# Reach_A0.net
KiCad netlist of a schematic drawn in EAGLE
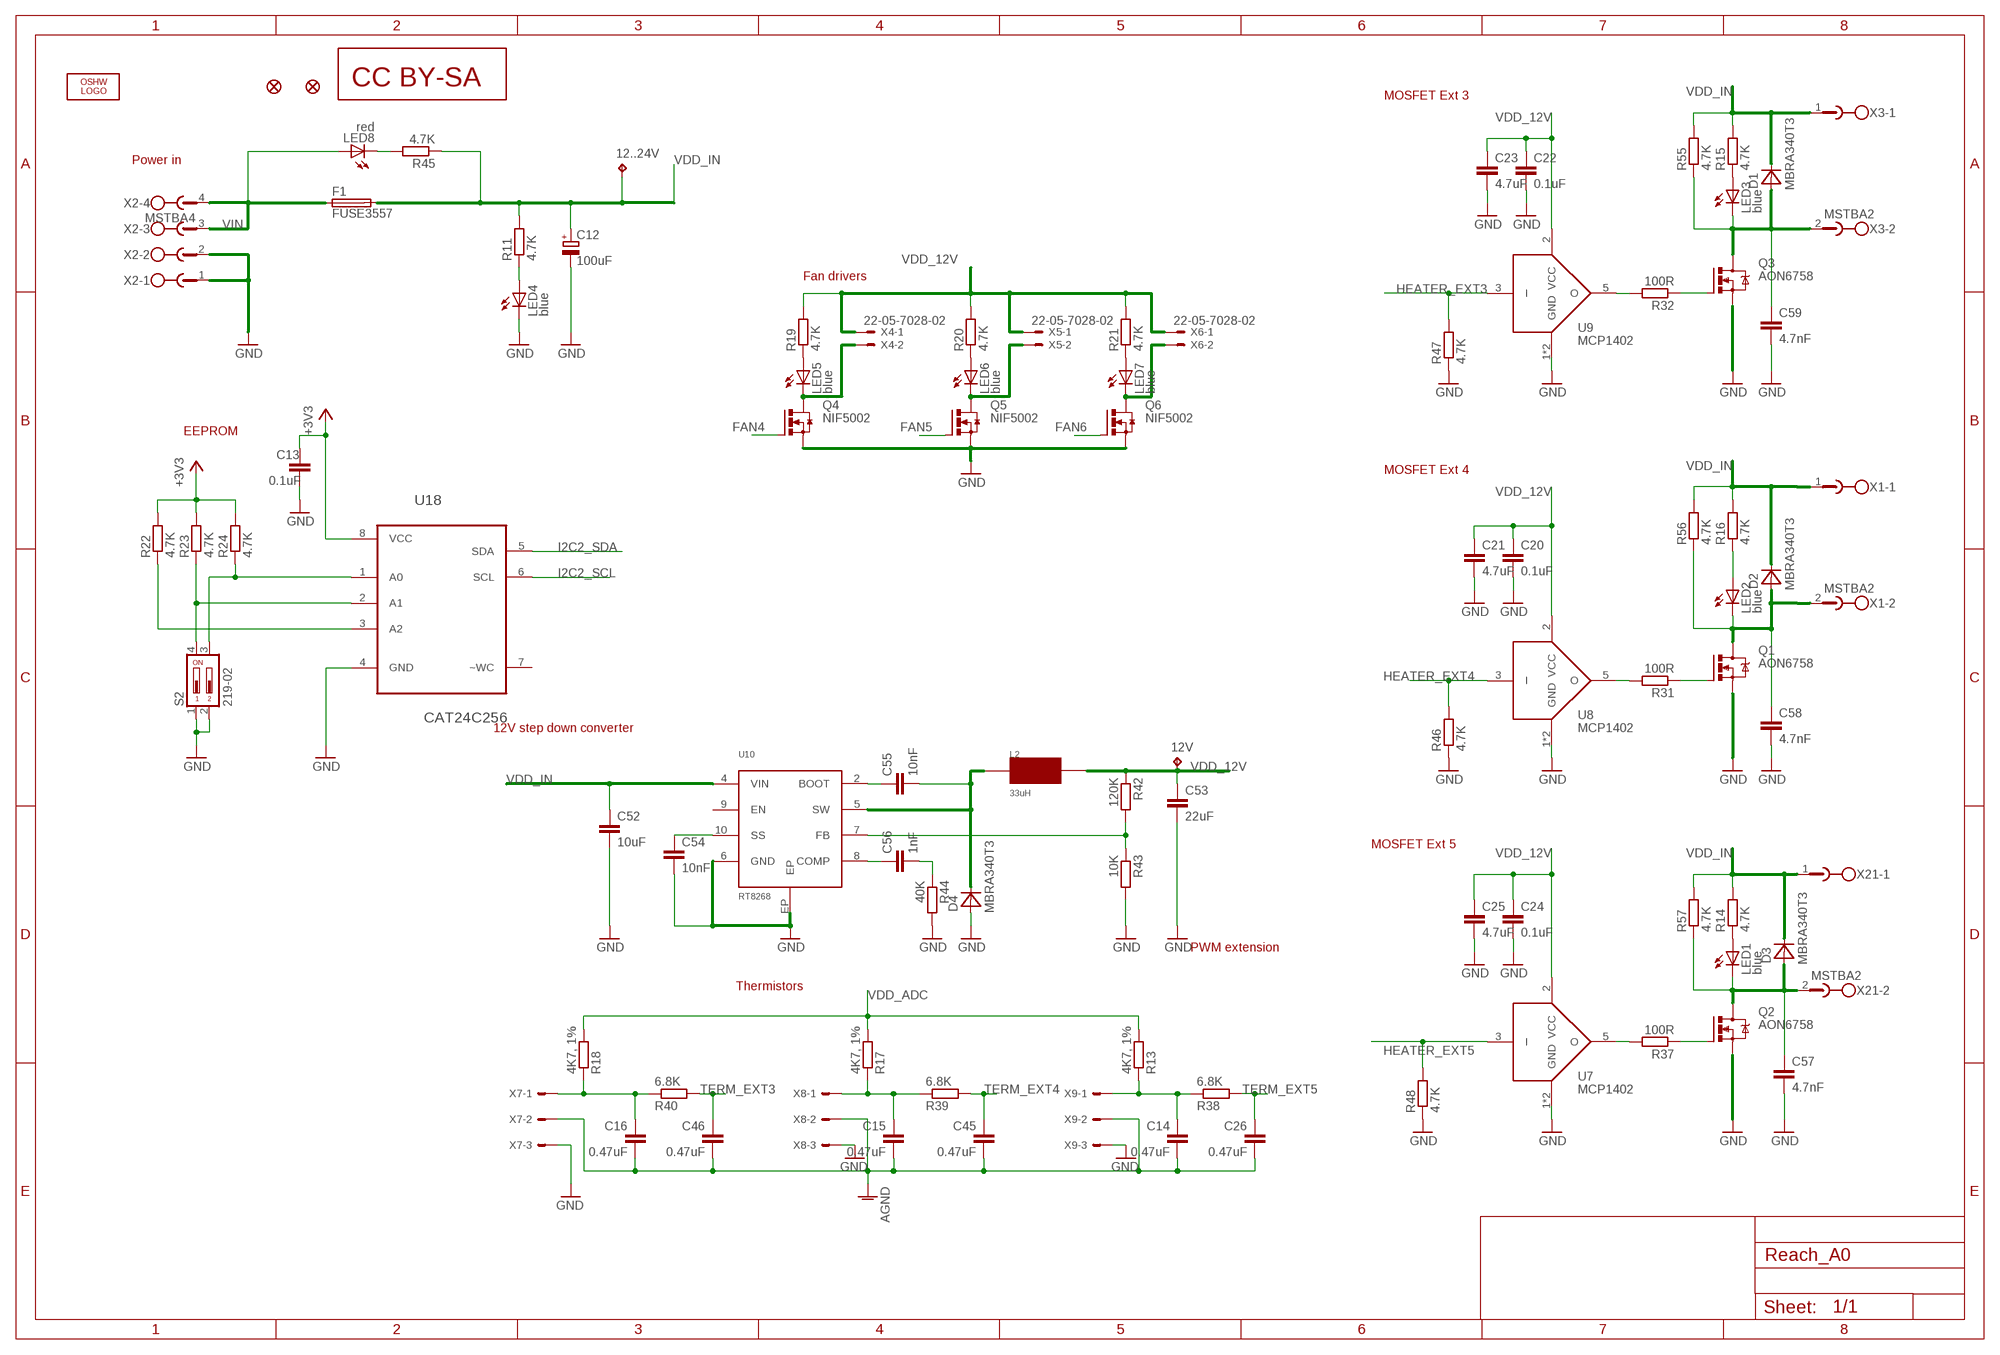
[diagram p0: schematic, sheet 1, part 1 of 2]
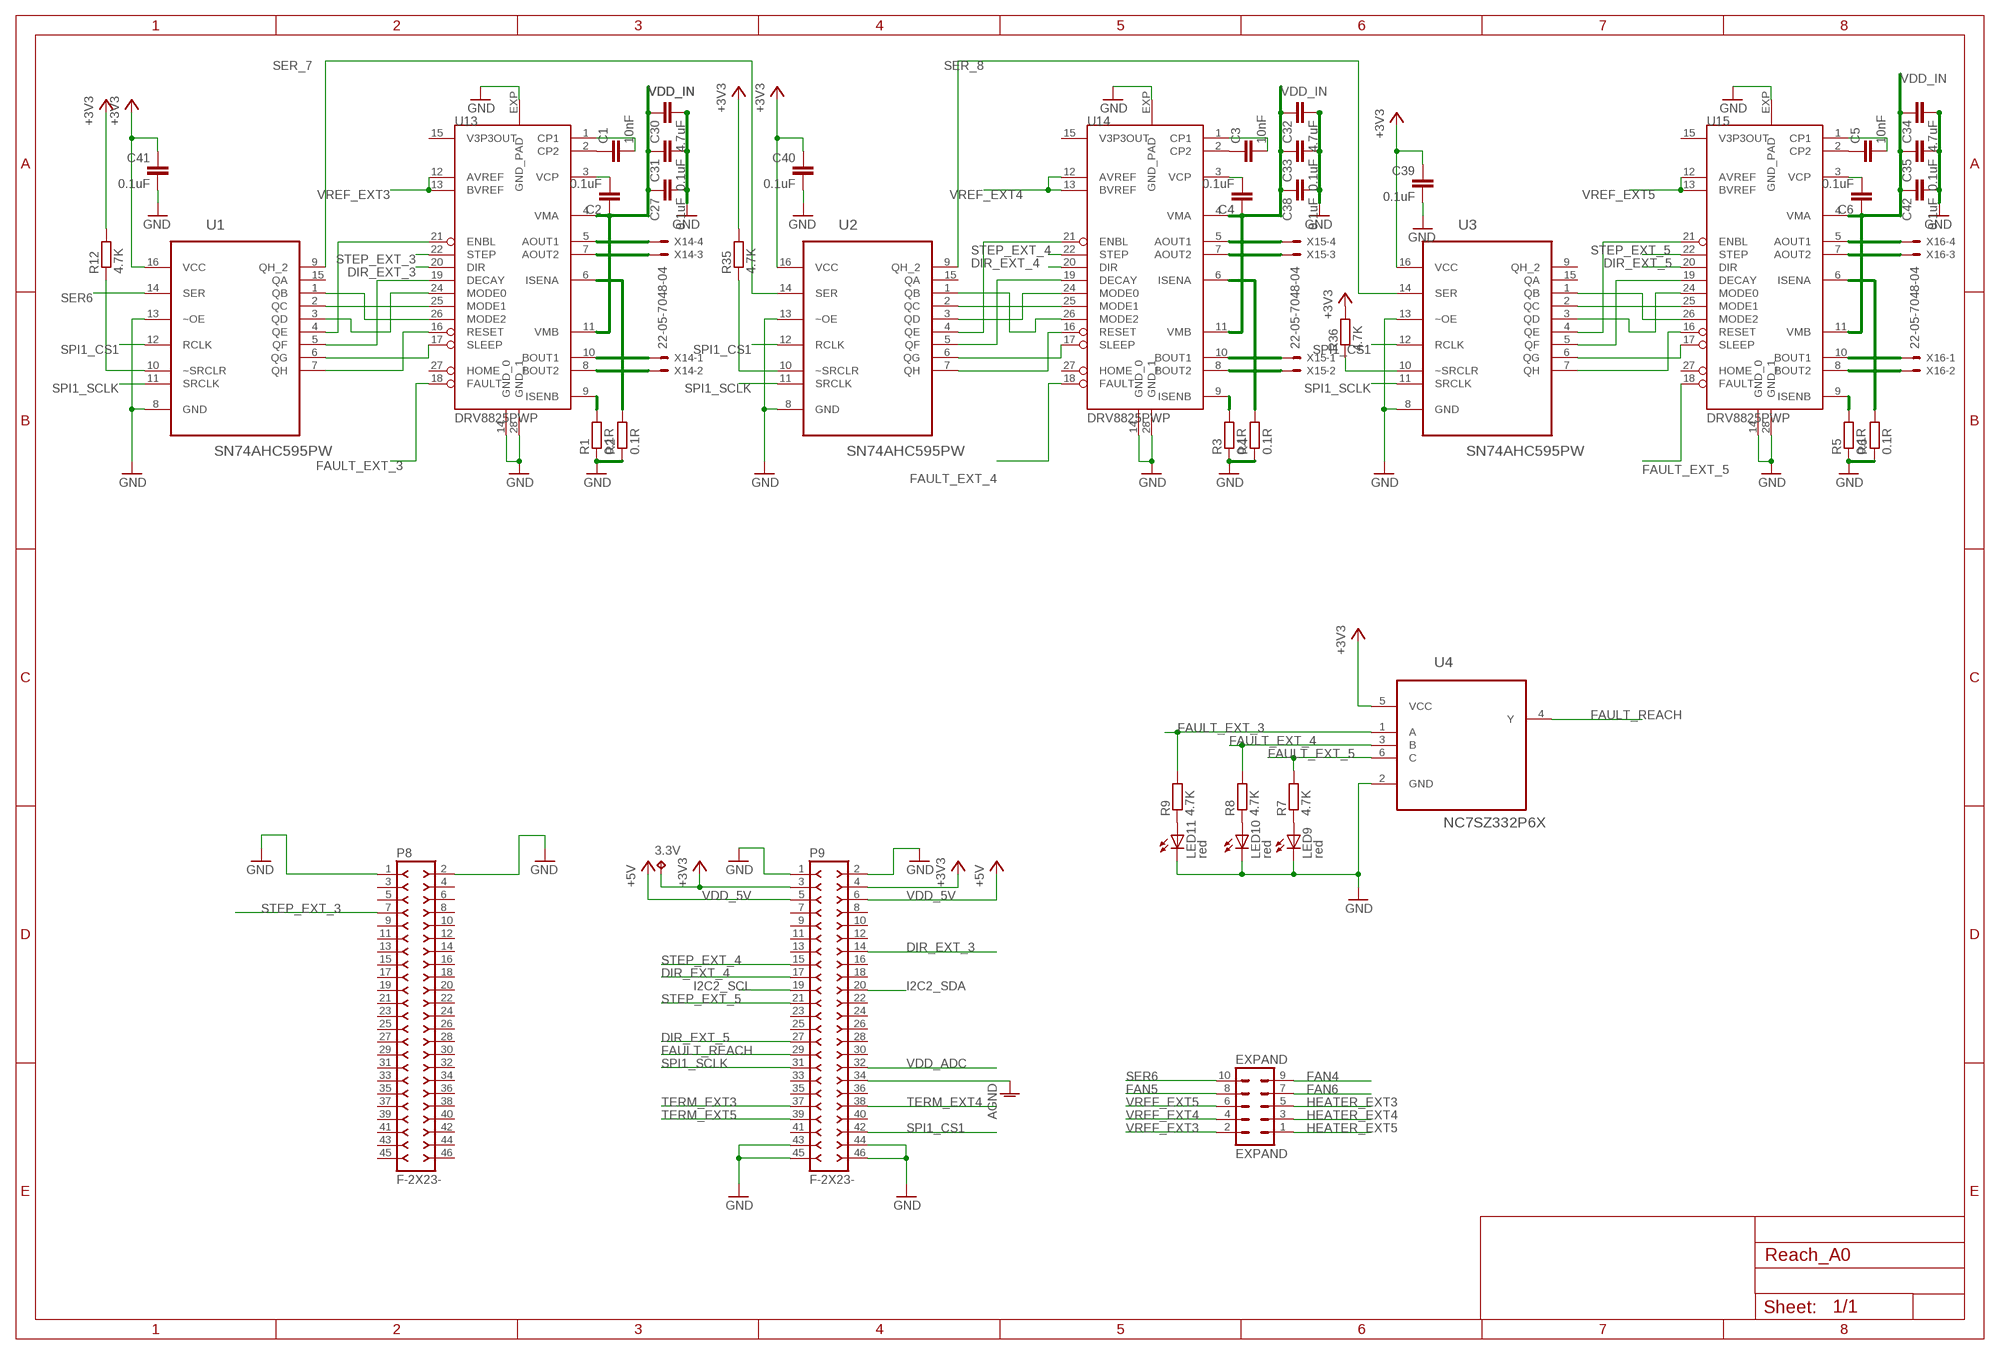
[diagram p1: schematic, sheet 1, part 2 of 2]

(export (version "E")
  (design (tool "Eeschema 10.0.6"))
  (components
    (comp (ref "3.3V")
      (value "TPB1,27")
      (footprint "eagle-import:B1,27")
      (libsource (lib "eagle-import") (part "TPB1,27"))
    )
    (comp (ref "12..24V")
      (value "TPB1,27")
      (footprint "eagle-import:B1,27")
      (libsource (lib "eagle-import") (part "TPB1,27"))
    )
    (comp (ref "12V")
      (value "TPB1,27")
      (footprint "eagle-import:B1,27")
      (libsource (lib "eagle-import") (part "TPB1,27"))
    )
    (comp (ref "C1")
      (value "10nF")
      (footprint "eagle-import:C0402")
      (libsource (lib "eagle-import") (part "C-EUC0402"))
    )
    (comp (ref "C2")
      (value "0.1uF")
      (footprint "eagle-import:C0402")
      (libsource (lib "eagle-import") (part "C-EUC0402"))
    )
    (comp (ref "C3")
      (value "10nF")
      (footprint "eagle-import:C0402")
      (libsource (lib "eagle-import") (part "C-EUC0402"))
    )
    (comp (ref "C4")
      (value "0.1uF")
      (footprint "eagle-import:C0402")
      (libsource (lib "eagle-import") (part "C-EUC0402"))
    )
    (comp (ref "C5")
      (value "10nF")
      (footprint "eagle-import:C0402")
      (libsource (lib "eagle-import") (part "C-EUC0402"))
    )
    (comp (ref "C6")
      (value "0.1uF")
      (footprint "eagle-import:C0402")
      (libsource (lib "eagle-import") (part "C-EUC0402"))
    )
    (comp (ref "C12")
      (value "100uF")
      (footprint "eagle-import:140CLH-0810")
      (libsource (lib "eagle-import") (part "CPOL-EU140CLH-0810"))
    )
    (comp (ref "C13")
      (value "0.1uF")
      (footprint "eagle-import:C0402")
      (libsource (lib "eagle-import") (part "C-EUC0402"))
    )
    (comp (ref "C14")
      (value "0.47uF")
      (footprint "eagle-import:C0402")
      (libsource (lib "eagle-import") (part "C-EUC0402"))
    )
    (comp (ref "C15")
      (value "0.47uF")
      (footprint "eagle-import:C0402")
      (libsource (lib "eagle-import") (part "C-EUC0402"))
    )
    (comp (ref "C16")
      (value "0.47uF")
      (footprint "eagle-import:C0402")
      (libsource (lib "eagle-import") (part "C-EUC0402"))
    )
    (comp (ref "C20")
      (value "0.1uF")
      (footprint "eagle-import:C0402")
      (libsource (lib "eagle-import") (part "C-EUC0402"))
    )
    (comp (ref "C21")
      (value "4.7uF")
      (footprint "eagle-import:C0402")
      (libsource (lib "eagle-import") (part "C-EUC0402"))
    )
    (comp (ref "C22")
      (value "0.1uF")
      (footprint "eagle-import:C0402")
      (libsource (lib "eagle-import") (part "C-EUC0402"))
    )
    (comp (ref "C23")
      (value "4.7uF")
      (footprint "eagle-import:C0402")
      (libsource (lib "eagle-import") (part "C-EUC0402"))
    )
    (comp (ref "C24")
      (value "0.1uF")
      (footprint "eagle-import:C0402")
      (libsource (lib "eagle-import") (part "C-EUC0402"))
    )
    (comp (ref "C25")
      (value "4.7uF")
      (footprint "eagle-import:C0402")
      (libsource (lib "eagle-import") (part "C-EUC0402"))
    )
    (comp (ref "C26")
      (value "0.47uF")
      (footprint "eagle-import:C0402")
      (libsource (lib "eagle-import") (part "C-EUC0402"))
    )
    (comp (ref "C27")
      (value "0.1uF")
      (footprint "eagle-import:C0402")
      (libsource (lib "eagle-import") (part "C-EUC0402"))
    )
    (comp (ref "C30")
      (value "4.7uF")
      (footprint "eagle-import:C0603")
      (libsource (lib "eagle-import") (part "C-EUC0603"))
    )
    (comp (ref "C31")
      (value "0.1uF")
      (footprint "eagle-import:C0402")
      (libsource (lib "eagle-import") (part "C-EUC0402"))
    )
    (comp (ref "C32")
      (value "4.7uF")
      (footprint "eagle-import:C0603")
      (libsource (lib "eagle-import") (part "C-EUC0603"))
    )
    (comp (ref "C33")
      (value "0.1uF")
      (footprint "eagle-import:C0402")
      (libsource (lib "eagle-import") (part "C-EUC0402"))
    )
    (comp (ref "C34")
      (value "4.7uF")
      (footprint "eagle-import:C0603")
      (libsource (lib "eagle-import") (part "C-EUC0603"))
    )
    (comp (ref "C35")
      (value "0.1uF")
      (footprint "eagle-import:C0402")
      (libsource (lib "eagle-import") (part "C-EUC0402"))
    )
    (comp (ref "C38")
      (value "0.1uF")
      (footprint "eagle-import:C0402")
      (libsource (lib "eagle-import") (part "C-EUC0402"))
    )
    (comp (ref "C39")
      (value "0.1uF")
      (footprint "eagle-import:C0402")
      (libsource (lib "eagle-import") (part "C-EUC0402"))
    )
    (comp (ref "C40")
      (value "0.1uF")
      (footprint "eagle-import:C0402")
      (libsource (lib "eagle-import") (part "C-EUC0402"))
    )
    (comp (ref "C41")
      (value "0.1uF")
      (footprint "eagle-import:C0402")
      (libsource (lib "eagle-import") (part "C-EUC0402"))
    )
    (comp (ref "C42")
      (value "0.1uF")
      (footprint "eagle-import:C0402")
      (libsource (lib "eagle-import") (part "C-EUC0402"))
    )
    (comp (ref "C45")
      (value "0.47uF")
      (footprint "eagle-import:C0402")
      (libsource (lib "eagle-import") (part "C-EUC0402"))
    )
    (comp (ref "C46")
      (value "0.47uF")
      (footprint "eagle-import:C0402")
      (libsource (lib "eagle-import") (part "C-EUC0402"))
    )
    (comp (ref "C52")
      (value "10uF")
      (footprint "eagle-import:C1206")
      (libsource (lib "eagle-import") (part "C-EUC1206"))
    )
    (comp (ref "C53")
      (value "22uF")
      (footprint "eagle-import:C0805")
      (libsource (lib "eagle-import") (part "C-EUC0805"))
    )
    (comp (ref "C54")
      (value "10nF")
      (footprint "eagle-import:C0402")
      (libsource (lib "eagle-import") (part "C-EUC0402"))
    )
    (comp (ref "C55")
      (value "10nF")
      (footprint "eagle-import:C0402")
      (libsource (lib "eagle-import") (part "C-EUC0402"))
    )
    (comp (ref "C56")
      (value "1nF")
      (footprint "eagle-import:C0402")
      (libsource (lib "eagle-import") (part "C-EUC0402"))
    )
    (comp (ref "C57")
      (value "4.7nF")
      (footprint "eagle-import:C0402")
      (libsource (lib "eagle-import") (part "C-EUC0402"))
    )
    (comp (ref "C58")
      (value "4.7nF")
      (footprint "eagle-import:C0402")
      (libsource (lib "eagle-import") (part "C-EUC0402"))
    )
    (comp (ref "C59")
      (value "4.7nF")
      (footprint "eagle-import:C0402")
      (libsource (lib "eagle-import") (part "C-EUC0402"))
    )
    (comp (ref "D1")
      (value "MBRA340T3")
      (footprint "eagle-import:SMA")
      (libsource (lib "eagle-import") (part "MBRA340T3"))
    )
    (comp (ref "D2")
      (value "MBRA340T3")
      (footprint "eagle-import:SMA")
      (libsource (lib "eagle-import") (part "MBRA340T3"))
    )
    (comp (ref "D3")
      (value "MBRA340T3")
      (footprint "eagle-import:SMA")
      (libsource (lib "eagle-import") (part "MBRA340T3"))
    )
    (comp (ref "D4")
      (value "MBRA340T3")
      (footprint "eagle-import:SMA")
      (libsource (lib "eagle-import") (part "MBRA340T3"))
    )
    (comp (ref "EXPAND")
      (value "EXPAND")
      (footprint "eagle-import:MA05-2")
      (libsource (lib "eagle-import") (part "MA05-2"))
    )
    (comp (ref "F1")
      (value "FUSE3557")
      (footprint "eagle-import:3557")
      (libsource (lib "eagle-import") (part "FUSE3557"))
    )
    (comp (ref "JP1")
      (value "FIDUCIAL1X2.5")
      (footprint "eagle-import:FIDUCIAL-1X2.5")
      (libsource (lib "eagle-import") (part "FIDUCIAL1X2.5"))
    )
    (comp (ref "JP2")
      (value "FIDUCIAL1X2.5")
      (footprint "eagle-import:FIDUCIAL-1X2.5")
      (libsource (lib "eagle-import") (part "FIDUCIAL1X2.5"))
    )
    (comp (ref "L2")
      (value "33uH")
      (footprint "eagle-import:NR8040T330")
      (libsource (lib "eagle-import") (part "RT8040T330"))
    )
    (comp (ref "LED1")
      (value "blue")
      (footprint "eagle-import:CHIP-LED0603")
      (libsource (lib "eagle-import") (part "LEDCHIP-LED0603"))
    )
    (comp (ref "LED2")
      (value "blue")
      (footprint "eagle-import:CHIP-LED0603")
      (libsource (lib "eagle-import") (part "LEDCHIP-LED0603"))
    )
    (comp (ref "LED3")
      (value "blue")
      (footprint "eagle-import:CHIP-LED0603")
      (libsource (lib "eagle-import") (part "LEDCHIP-LED0603"))
    )
    (comp (ref "LED4")
      (value "blue")
      (footprint "eagle-import:CHIP-LED0603")
      (libsource (lib "eagle-import") (part "LEDCHIP-LED0603"))
    )
    (comp (ref "LED5")
      (value "blue")
      (footprint "eagle-import:CHIP-LED0603")
      (libsource (lib "eagle-import") (part "LEDCHIP-LED0603"))
    )
    (comp (ref "LED6")
      (value "blue")
      (footprint "eagle-import:CHIP-LED0603")
      (libsource (lib "eagle-import") (part "LEDCHIP-LED0603"))
    )
    (comp (ref "LED7")
      (value "blue")
      (footprint "eagle-import:CHIP-LED0603")
      (libsource (lib "eagle-import") (part "LEDCHIP-LED0603"))
    )
    (comp (ref "LED8")
      (value "red")
      (footprint "eagle-import:CHIP-LED0603")
      (libsource (lib "eagle-import") (part "LEDCHIP-LED0603"))
    )
    (comp (ref "LED9")
      (value "red")
      (footprint "eagle-import:CHIP-LED0603")
      (libsource (lib "eagle-import") (part "LEDCHIP-LED0603"))
    )
    (comp (ref "LED10")
      (value "red")
      (footprint "eagle-import:CHIP-LED0603")
      (libsource (lib "eagle-import") (part "LEDCHIP-LED0603"))
    )
    (comp (ref "LED11")
      (value "red")
      (footprint "eagle-import:CHIP-LED0603")
      (libsource (lib "eagle-import") (part "LEDCHIP-LED0603"))
    )
    (comp (ref "LOGO1")
      (value "OSHW_LOGO_FILLX0200-NT")
      (footprint "eagle-import:OSHW_FILLX200_NOTEXT")
      (libsource (lib "eagle-import") (part "OSHW_LOGO_FILLX0200-NT"))
    )
    (comp (ref "P8")
      (value "F-2X23-")
      (footprint "eagle-import:DIL-100-2X23")
      (libsource (lib "eagle-import") (part "F-2X23-"))
    )
    (comp (ref "P9")
      (value "F-2X23-")
      (footprint "eagle-import:DIL-100-2X23")
      (libsource (lib "eagle-import") (part "F-2X23-"))
    )
    (comp (ref "Q1")
      (value "AON6758")
      (footprint "eagle-import:8-DFN-EP-(5X6)")
      (libsource (lib "eagle-import") (part "AON6758"))
    )
    (comp (ref "Q2")
      (value "AON6758")
      (footprint "eagle-import:8-DFN-EP-(5X6)")
      (libsource (lib "eagle-import") (part "AON6758"))
    )
    (comp (ref "Q3")
      (value "AON6758")
      (footprint "eagle-import:8-DFN-EP-(5X6)")
      (libsource (lib "eagle-import") (part "AON6758"))
    )
    (comp (ref "Q4")
      (value "NIF5002")
      (footprint "eagle-import:SOT223")
      (libsource (lib "eagle-import") (part "N-HEXFET-2D_?-SOT232"))
    )
    (comp (ref "Q5")
      (value "NIF5002")
      (footprint "eagle-import:SOT223")
      (libsource (lib "eagle-import") (part "N-HEXFET-2D_?-SOT232"))
    )
    (comp (ref "Q6")
      (value "NIF5002")
      (footprint "eagle-import:SOT223")
      (libsource (lib "eagle-import") (part "N-HEXFET-2D_?-SOT232"))
    )
    (comp (ref "R1")
      (value "0.1R")
      (footprint "eagle-import:R0805")
      (libsource (lib "eagle-import") (part "R-EU_R0805"))
    )
    (comp (ref "R2")
      (value "0.1R")
      (footprint "eagle-import:R0805")
      (libsource (lib "eagle-import") (part "R-EU_R0805"))
    )
    (comp (ref "R3")
      (value "0.1R")
      (footprint "eagle-import:R0805")
      (libsource (lib "eagle-import") (part "R-EU_R0805"))
    )
    (comp (ref "R4")
      (value "0.1R")
      (footprint "eagle-import:R0805")
      (libsource (lib "eagle-import") (part "R-EU_R0805"))
    )
    (comp (ref "R5")
      (value "0.1R")
      (footprint "eagle-import:R0805")
      (libsource (lib "eagle-import") (part "R-EU_R0805"))
    )
    (comp (ref "R6")
      (value "0.1R")
      (footprint "eagle-import:R0805")
      (libsource (lib "eagle-import") (part "R-EU_R0805"))
    )
    (comp (ref "R7")
      (value "4.7K")
      (footprint "eagle-import:R0402")
      (libsource (lib "eagle-import") (part "R-EU_R0402"))
    )
    (comp (ref "R8")
      (value "4.7K")
      (footprint "eagle-import:R0402")
      (libsource (lib "eagle-import") (part "R-EU_R0402"))
    )
    (comp (ref "R9")
      (value "4.7K")
      (footprint "eagle-import:R0402")
      (libsource (lib "eagle-import") (part "R-EU_R0402"))
    )
    (comp (ref "R11")
      (value "4.7K")
      (footprint "eagle-import:R0402")
      (libsource (lib "eagle-import") (part "R-EU_R0402"))
    )
    (comp (ref "R12")
      (value "4.7K")
      (footprint "eagle-import:R0402")
      (libsource (lib "eagle-import") (part "R-EU_R0402"))
    )
    (comp (ref "R13")
      (value "4K7, 1%")
      (footprint "eagle-import:R0402")
      (libsource (lib "eagle-import") (part "R-EU_R0402"))
    )
    (comp (ref "R14")
      (value "4.7K")
      (footprint "eagle-import:R0402")
      (libsource (lib "eagle-import") (part "R-EU_R0402"))
    )
    (comp (ref "R15")
      (value "4.7K")
      (footprint "eagle-import:R0402")
      (libsource (lib "eagle-import") (part "R-EU_R0402"))
    )
    (comp (ref "R16")
      (value "4.7K")
      (footprint "eagle-import:R0402")
      (libsource (lib "eagle-import") (part "R-EU_R0402"))
    )
    (comp (ref "R17")
      (value "4K7, 1%")
      (footprint "eagle-import:R0402")
      (libsource (lib "eagle-import") (part "R-EU_R0402"))
    )
    (comp (ref "R18")
      (value "4K7, 1%")
      (footprint "eagle-import:R0402")
      (libsource (lib "eagle-import") (part "R-EU_R0402"))
    )
    (comp (ref "R19")
      (value "4.7K")
      (footprint "eagle-import:R0402")
      (libsource (lib "eagle-import") (part "R-EU_R0402"))
    )
    (comp (ref "R20")
      (value "4.7K")
      (footprint "eagle-import:R0402")
      (libsource (lib "eagle-import") (part "R-EU_R0402"))
    )
    (comp (ref "R21")
      (value "4.7K")
      (footprint "eagle-import:R0402")
      (libsource (lib "eagle-import") (part "R-EU_R0402"))
    )
    (comp (ref "R22")
      (value "4.7K")
      (footprint "eagle-import:R0402")
      (libsource (lib "eagle-import") (part "R-EU_R0402"))
    )
    (comp (ref "R23")
      (value "4.7K")
      (footprint "eagle-import:R0402")
      (libsource (lib "eagle-import") (part "R-EU_R0402"))
    )
    (comp (ref "R24")
      (value "4.7K")
      (footprint "eagle-import:R0402")
      (libsource (lib "eagle-import") (part "R-EU_R0402"))
    )
    (comp (ref "R31")
      (value "100R")
      (footprint "eagle-import:R0402")
      (libsource (lib "eagle-import") (part "R-EU_R0402"))
    )
    (comp (ref "R32")
      (value "100R")
      (footprint "eagle-import:R0402")
      (libsource (lib "eagle-import") (part "R-EU_R0402"))
    )
    (comp (ref "R35")
      (value "4.7K")
      (footprint "eagle-import:R0402")
      (libsource (lib "eagle-import") (part "R-EU_R0402"))
    )
    (comp (ref "R36")
      (value "4.7K")
      (footprint "eagle-import:R0402")
      (libsource (lib "eagle-import") (part "R-EU_R0402"))
    )
    (comp (ref "R37")
      (value "100R")
      (footprint "eagle-import:R0402")
      (libsource (lib "eagle-import") (part "R-EU_R0402"))
    )
    (comp (ref "R38")
      (value "6.8K")
      (footprint "eagle-import:R0402")
      (libsource (lib "eagle-import") (part "R-EU_R0402"))
    )
    (comp (ref "R39")
      (value "6.8K")
      (footprint "eagle-import:R0402")
      (libsource (lib "eagle-import") (part "R-EU_R0402"))
    )
    (comp (ref "R40")
      (value "6.8K")
      (footprint "eagle-import:R0402")
      (libsource (lib "eagle-import") (part "R-EU_R0402"))
    )
    (comp (ref "R42")
      (value "120K")
      (footprint "eagle-import:R0402")
      (libsource (lib "eagle-import") (part "R-EU_R0402"))
    )
    (comp (ref "R43")
      (value "10K")
      (footprint "eagle-import:R0402")
      (libsource (lib "eagle-import") (part "R-EU_R0402"))
    )
    (comp (ref "R44")
      (value "40K")
      (footprint "eagle-import:R0402")
      (libsource (lib "eagle-import") (part "R-EU_R0402"))
    )
    (comp (ref "R45")
      (value "4.7K")
      (footprint "eagle-import:R0402")
      (libsource (lib "eagle-import") (part "R-EU_R0402"))
    )
    (comp (ref "R46")
      (value "4.7K")
      (footprint "eagle-import:R0402")
      (libsource (lib "eagle-import") (part "R-EU_R0402"))
    )
    (comp (ref "R47")
      (value "4.7K")
      (footprint "eagle-import:R0402")
      (libsource (lib "eagle-import") (part "R-EU_R0402"))
    )
    (comp (ref "R48")
      (value "4.7K")
      (footprint "eagle-import:R0402")
      (libsource (lib "eagle-import") (part "R-EU_R0402"))
    )
    (comp (ref "R55")
      (value "4.7K")
      (footprint "eagle-import:R0402")
      (libsource (lib "eagle-import") (part "R-EU_R0402"))
    )
    (comp (ref "R56")
      (value "4.7K")
      (footprint "eagle-import:R0402")
      (libsource (lib "eagle-import") (part "R-EU_R0402"))
    )
    (comp (ref "R57")
      (value "4.7K")
      (footprint "eagle-import:R0402")
      (libsource (lib "eagle-import") (part "R-EU_R0402"))
    )
    (comp (ref "S2")
      (value "219-02")
      (footprint "eagle-import:CTS-219-02")
      (libsource (lib "eagle-import") (part "219-02"))
    )
    (comp (ref "U$3")
      (value "CC-BY-SA")
      (footprint "eagle-import:CC-BY-SA")
      (libsource (lib "eagle-import") (part "CC-BY-SA"))
    )
    (comp (ref "U1")
      (value "SN74AHC595PW")
      (footprint "eagle-import:SOP65P640X120-16N")
      (libsource (lib "eagle-import") (part "SN74AHC595PW"))
    )
    (comp (ref "U2")
      (value "SN74AHC595PW")
      (footprint "eagle-import:SOP65P640X120-16N")
      (libsource (lib "eagle-import") (part "SN74AHC595PW"))
    )
    (comp (ref "U3")
      (value "SN74AHC595PW")
      (footprint "eagle-import:SOP65P640X120-16N")
      (libsource (lib "eagle-import") (part "SN74AHC595PW"))
    )
    (comp (ref "U4")
      (value "NC7SZ332P6X")
      (footprint "eagle-import:SOT65P210X110-6N")
      (libsource (lib "eagle-import") (part "NC7SZ332P6X"))
    )
    (comp (ref "U7")
      (value "MCP1402")
      (footprint "eagle-import:SOT23-5L")
      (libsource (lib "eagle-import") (part "MCP1402"))
    )
    (comp (ref "U8")
      (value "MCP1402")
      (footprint "eagle-import:SOT23-5L")
      (libsource (lib "eagle-import") (part "MCP1402"))
    )
    (comp (ref "U9")
      (value "MCP1402")
      (footprint "eagle-import:SOT23-5L")
      (libsource (lib "eagle-import") (part "MCP1402"))
    )
    (comp (ref "U10")
      (value "RT8268")
      (footprint "eagle-import:MSOP10")
      (libsource (lib "eagle-import") (part "RT8268"))
    )
    (comp (ref "U13")
      (value "DRV8825PWP")
      (footprint "eagle-import:TSSOP-28")
      (libsource (lib "eagle-import") (part "DRV8825PWP"))
    )
    (comp (ref "U14")
      (value "DRV8825PWP")
      (footprint "eagle-import:TSSOP-28")
      (libsource (lib "eagle-import") (part "DRV8825PWP"))
    )
    (comp (ref "U15")
      (value "DRV8825PWP")
      (footprint "eagle-import:TSSOP-28")
      (libsource (lib "eagle-import") (part "DRV8825PWP"))
    )
    (comp (ref "U18")
      (value "CAT24C256")
      (footprint "eagle-import:SOIC127P600X175-8N")
      (libsource (lib "eagle-import") (part "CAT24C256"))
    )
    (comp (ref "X1")
      (value "MSTBA2")
      (footprint "eagle-import:MSTBA2")
      (libsource (lib "eagle-import") (part "MSTBA2"))
    )
    (comp (ref "X2")
      (value "MSTBA4")
      (footprint "eagle-import:MSTBA4")
      (libsource (lib "eagle-import") (part "MSTBA4"))
    )
    (comp (ref "X3")
      (value "MSTBA2")
      (footprint "eagle-import:MSTBA2")
      (libsource (lib "eagle-import") (part "MSTBA2"))
    )
    (comp (ref "X4")
      (value "22-05-7028-02")
      (footprint "eagle-import:7395-02")
      (libsource (lib "eagle-import") (part "22-?-0205-7028"))
    )
    (comp (ref "X5")
      (value "22-05-7028-02")
      (footprint "eagle-import:7395-02")
      (libsource (lib "eagle-import") (part "22-?-0205-7028"))
    )
    (comp (ref "X6")
      (value "22-05-7028-02")
      (footprint "eagle-import:7395-02")
      (libsource (lib "eagle-import") (part "22-?-0205-7028"))
    )
    (comp (ref "X7")
      (value "22-05-7038-03")
      (footprint "eagle-import:7395-03")
      (libsource (lib "eagle-import") (part "22-?-0305-7038"))
    )
    (comp (ref "X8")
      (value "22-05-7038-03")
      (footprint "eagle-import:7395-03")
      (libsource (lib "eagle-import") (part "22-?-0305-7038"))
    )
    (comp (ref "X9")
      (value "22-05-7038-03")
      (footprint "eagle-import:7395-03")
      (libsource (lib "eagle-import") (part "22-?-0305-7038"))
    )
    (comp (ref "X14")
      (value "22-05-7048-04")
      (footprint "eagle-import:7395-04")
      (libsource (lib "eagle-import") (part "22-?-0405-7048"))
    )
    (comp (ref "X15")
      (value "22-05-7048-04")
      (footprint "eagle-import:7395-04")
      (libsource (lib "eagle-import") (part "22-?-0405-7048"))
    )
    (comp (ref "X16")
      (value "22-05-7048-04")
      (footprint "eagle-import:7395-04")
      (libsource (lib "eagle-import") (part "22-?-0405-7048"))
    )
    (comp (ref "X21")
      (value "MSTBA2")
      (footprint "eagle-import:MSTBA2")
      (libsource (lib "eagle-import") (part "MSTBA2"))
    )
  )
  (nets
    (net (code "1") (name "+3V3") (class "Default")
      (node (ref "3.3V") (pin "TP") (pinfunction "TP_TP") (pintype "input"))
      (node (ref "C13") (pin "1") (pinfunction "1_1") (pintype "passive"))
      (node (ref "C39") (pin "1") (pinfunction "1_1") (pintype "passive"))
      (node (ref "C40") (pin "1") (pinfunction "1_1") (pintype "passive"))
      (node (ref "C41") (pin "1") (pinfunction "1_1") (pintype "passive"))
      (node (ref "P9") (pin "3") (pinfunction "3_3") (pintype "passive"))
      (node (ref "P9") (pin "4") (pinfunction "4_4") (pintype "passive"))
      (node (ref "R12") (pin "2") (pinfunction "2_2") (pintype "passive"))
      (node (ref "R22") (pin "2") (pinfunction "2_2") (pintype "passive"))
      (node (ref "R23") (pin "2") (pinfunction "2_2") (pintype "passive"))
      (node (ref "R24") (pin "2") (pinfunction "2_2") (pintype "passive"))
      (node (ref "R35") (pin "2") (pinfunction "2_2") (pintype "passive"))
      (node (ref "R36") (pin "2") (pinfunction "2_2") (pintype "passive"))
      (node (ref "U1") (pin "16") (pinfunction "VCC_16") (pintype "power_in"))
      (node (ref "U18") (pin "8") (pinfunction "VCC_8") (pintype "power_in"))
      (node (ref "U2") (pin "16") (pinfunction "VCC_16") (pintype "power_in"))
      (node (ref "U3") (pin "16") (pinfunction "VCC_16") (pintype "power_in"))
      (node (ref "U4") (pin "5") (pinfunction "VCC_5") (pintype "power_in"))
    )
    (net (code "2") (name "+5V") (class "Default")
      (node (ref "P9") (pin "5") (pinfunction "5_5") (pintype "passive"))
      (node (ref "P9") (pin "6") (pinfunction "6_6") (pintype "passive"))
    )
    (net (code "3") (name "/DIR_EXT_3") (class "Default")
      (node (ref "P9") (pin "14") (pinfunction "14_14") (pintype "passive"))
      (node (ref "U13") (pin "20") (pinfunction "DIR_20") (pintype "input"))
    )
    (net (code "4") (name "/DIR_EXT_4") (class "Default")
      (node (ref "P9") (pin "17") (pinfunction "17_17") (pintype "passive"))
      (node (ref "U14") (pin "20") (pinfunction "DIR_20") (pintype "input"))
    )
    (net (code "5") (name "/DIR_EXT_5") (class "Default")
      (node (ref "P9") (pin "27") (pinfunction "27_27") (pintype "passive"))
      (node (ref "U15") (pin "20") (pinfunction "DIR_20") (pintype "input"))
    )
    (net (code "6") (name "/FAN4") (class "Default")
      (node (ref "EXPAND") (pin "9") (pinfunction "9_9") (pintype "passive"))
      (node (ref "Q4") (pin "1") (pinfunction "G_1") (pintype "passive"))
    )
    (net (code "7") (name "/FAN5") (class "Default")
      (node (ref "EXPAND") (pin "8") (pinfunction "8_8") (pintype "passive"))
      (node (ref "Q5") (pin "1") (pinfunction "G_1") (pintype "passive"))
    )
    (net (code "8") (name "/FAN6") (class "Default")
      (node (ref "EXPAND") (pin "7") (pinfunction "7_7") (pintype "passive"))
      (node (ref "Q6") (pin "1") (pinfunction "G_1") (pintype "passive"))
    )
    (net (code "9") (name "/FAULT_EXT_3") (class "Default")
      (node (ref "R9") (pin "2") (pinfunction "2_2") (pintype "passive"))
      (node (ref "U13") (pin "18") (pinfunction "FAULT_18") (pintype "output"))
      (node (ref "U4") (pin "1") (pinfunction "A_1") (pintype "input"))
    )
    (net (code "10") (name "/FAULT_EXT_4") (class "Default")
      (node (ref "R8") (pin "2") (pinfunction "2_2") (pintype "passive"))
      (node (ref "U14") (pin "18") (pinfunction "FAULT_18") (pintype "output"))
      (node (ref "U4") (pin "3") (pinfunction "B_3") (pintype "input"))
    )
    (net (code "11") (name "/FAULT_EXT_5") (class "Default")
      (node (ref "R7") (pin "2") (pinfunction "2_2") (pintype "passive"))
      (node (ref "U15") (pin "18") (pinfunction "FAULT_18") (pintype "output"))
      (node (ref "U4") (pin "6") (pinfunction "C_6") (pintype "input"))
    )
    (net (code "12") (name "/FAULT_REACH") (class "Default")
      (node (ref "P9") (pin "29") (pinfunction "29_29") (pintype "passive"))
      (node (ref "U4") (pin "4") (pinfunction "Y_4") (pintype "output"))
    )
    (net (code "13") (name "/HEATER_EXT3") (class "Default")
      (node (ref "EXPAND") (pin "5") (pinfunction "5_5") (pintype "passive"))
      (node (ref "R47") (pin "2") (pinfunction "2_2") (pintype "passive"))
      (node (ref "U9") (pin "3") (pinfunction "I_3") (pintype "input"))
    )
    (net (code "14") (name "/HEATER_EXT4") (class "Default")
      (node (ref "EXPAND") (pin "3") (pinfunction "3_3") (pintype "passive"))
      (node (ref "R46") (pin "2") (pinfunction "2_2") (pintype "passive"))
      (node (ref "U8") (pin "3") (pinfunction "I_3") (pintype "input"))
    )
    (net (code "15") (name "/HEATER_EXT5") (class "Default")
      (node (ref "EXPAND") (pin "1") (pinfunction "1_1") (pintype "passive"))
      (node (ref "R48") (pin "2") (pinfunction "2_2") (pintype "passive"))
      (node (ref "U7") (pin "3") (pinfunction "I_3") (pintype "input"))
    )
    (net (code "16") (name "/I2C2_SCL") (class "Default")
      (node (ref "P9") (pin "19") (pinfunction "19_19") (pintype "passive"))
      (node (ref "U18") (pin "6") (pinfunction "SCL_6") (pintype "input"))
    )
    (net (code "17") (name "/I2C2_SDA") (class "Default")
      (node (ref "P9") (pin "20") (pinfunction "20_20") (pintype "passive"))
      (node (ref "U18") (pin "5") (pinfunction "SDA_5") (pintype "bidirectional"))
    )
    (net (code "18") (name "/SER6") (class "Default")
      (node (ref "EXPAND") (pin "10") (pinfunction "10_10") (pintype "passive"))
      (node (ref "U1") (pin "14") (pinfunction "SER_14") (pintype "input"))
    )
    (net (code "19") (name "/SER_7") (class "Default")
      (node (ref "U1") (pin "9") (pinfunction "QH_2_9") (pintype "output"))
      (node (ref "U2") (pin "14") (pinfunction "SER_14") (pintype "input"))
    )
    (net (code "20") (name "/SER_8") (class "Default")
      (node (ref "U2") (pin "9") (pinfunction "QH_2_9") (pintype "output"))
      (node (ref "U3") (pin "14") (pinfunction "SER_14") (pintype "input"))
    )
    (net (code "21") (name "/SPI1_CS1") (class "Default")
      (node (ref "P9") (pin "42") (pinfunction "42_42") (pintype "passive"))
      (node (ref "U1") (pin "12") (pinfunction "RCLK_12") (pintype "input"))
      (node (ref "U2") (pin "12") (pinfunction "RCLK_12") (pintype "input"))
      (node (ref "U3") (pin "12") (pinfunction "RCLK_12") (pintype "input"))
    )
    (net (code "22") (name "/SPI1_SCLK") (class "Default")
      (node (ref "P9") (pin "31") (pinfunction "31_31") (pintype "passive"))
      (node (ref "U1") (pin "11") (pinfunction "SRCLK_11") (pintype "input"))
      (node (ref "U2") (pin "11") (pinfunction "SRCLK_11") (pintype "input"))
      (node (ref "U3") (pin "11") (pinfunction "SRCLK_11") (pintype "input"))
    )
    (net (code "23") (name "/STEP_EXT_3") (class "Default")
      (node (ref "P8") (pin "7") (pinfunction "7_7") (pintype "passive"))
      (node (ref "U13") (pin "22") (pinfunction "STEP_22") (pintype "input"))
    )
    (net (code "24") (name "/STEP_EXT_4") (class "Default")
      (node (ref "P9") (pin "15") (pinfunction "15_15") (pintype "passive"))
      (node (ref "U14") (pin "22") (pinfunction "STEP_22") (pintype "input"))
    )
    (net (code "25") (name "/STEP_EXT_5") (class "Default")
      (node (ref "P9") (pin "21") (pinfunction "21_21") (pintype "passive"))
      (node (ref "U15") (pin "22") (pinfunction "STEP_22") (pintype "input"))
    )
    (net (code "26") (name "/TERM_EXT3") (class "Default")
      (node (ref "C46") (pin "1") (pinfunction "1_1") (pintype "passive"))
      (node (ref "P9") (pin "37") (pinfunction "37_37") (pintype "passive"))
      (node (ref "R40") (pin "2") (pinfunction "2_2") (pintype "passive"))
    )
    (net (code "27") (name "/TERM_EXT4") (class "Default")
      (node (ref "C45") (pin "1") (pinfunction "1_1") (pintype "passive"))
      (node (ref "P9") (pin "38") (pinfunction "38_38") (pintype "passive"))
      (node (ref "R39") (pin "2") (pinfunction "2_2") (pintype "passive"))
    )
    (net (code "28") (name "/TERM_EXT5") (class "Default")
      (node (ref "C26") (pin "1") (pinfunction "1_1") (pintype "passive"))
      (node (ref "P9") (pin "39") (pinfunction "39_39") (pintype "passive"))
      (node (ref "R38") (pin "2") (pinfunction "2_2") (pintype "passive"))
    )
    (net (code "29") (name "/VDD_12V") (class "Default")
      (node (ref "12V") (pin "TP") (pinfunction "TP_TP") (pintype "input"))
      (node (ref "C20") (pin "1") (pinfunction "1_1") (pintype "passive"))
      (node (ref "C21") (pin "1") (pinfunction "1_1") (pintype "passive"))
      (node (ref "C22") (pin "1") (pinfunction "1_1") (pintype "passive"))
      (node (ref "C23") (pin "1") (pinfunction "1_1") (pintype "passive"))
      (node (ref "C24") (pin "1") (pinfunction "1_1") (pintype "passive"))
      (node (ref "C25") (pin "1") (pinfunction "1_1") (pintype "passive"))
      (node (ref "C53") (pin "1") (pinfunction "1_1") (pintype "passive"))
      (node (ref "L2") (pin "P$1") (pinfunction "P$1_P$1") (pintype "passive"))
      (node (ref "R19") (pin "2") (pinfunction "2_2") (pintype "passive"))
      (node (ref "R20") (pin "2") (pinfunction "2_2") (pintype "passive"))
      (node (ref "R21") (pin "2") (pinfunction "2_2") (pintype "passive"))
      (node (ref "R42") (pin "1") (pinfunction "1_1") (pintype "passive"))
      (node (ref "U7") (pin "2") (pinfunction "VCC_2") (pintype "power_in"))
      (node (ref "U8") (pin "2") (pinfunction "VCC_2") (pintype "power_in"))
      (node (ref "U9") (pin "2") (pinfunction "VCC_2") (pintype "power_in"))
      (node (ref "X4") (pin "1") (pinfunction "S_1") (pintype "passive"))
      (node (ref "X5") (pin "1") (pinfunction "S_1") (pintype "passive"))
      (node (ref "X6") (pin "1") (pinfunction "S_1") (pintype "passive"))
    )
    (net (code "30") (name "/VDD_ADC") (class "Default")
      (node (ref "P9") (pin "32") (pinfunction "32_32") (pintype "passive"))
      (node (ref "R13") (pin "2") (pinfunction "2_2") (pintype "passive"))
      (node (ref "R17") (pin "2") (pinfunction "2_2") (pintype "passive"))
      (node (ref "R18") (pin "2") (pinfunction "2_2") (pintype "passive"))
    )
    (net (code "31") (name "/VDD_IN") (class "Default")
      (node (ref "12..24V") (pin "TP") (pinfunction "TP_TP") (pintype "input"))
      (node (ref "C12") (pin "+") (pinfunction "+_+") (pintype "passive"))
      (node (ref "C2") (pin "1") (pinfunction "1_1") (pintype "passive"))
      (node (ref "C27") (pin "1") (pinfunction "1_1") (pintype "passive"))
      (node (ref "C30") (pin "1") (pinfunction "1_1") (pintype "passive"))
      (node (ref "C31") (pin "1") (pinfunction "1_1") (pintype "passive"))
      (node (ref "C32") (pin "1") (pinfunction "1_1") (pintype "passive"))
      (node (ref "C33") (pin "1") (pinfunction "1_1") (pintype "passive"))
      (node (ref "C34") (pin "1") (pinfunction "1_1") (pintype "passive"))
      (node (ref "C35") (pin "1") (pinfunction "1_1") (pintype "passive"))
      (node (ref "C38") (pin "1") (pinfunction "1_1") (pintype "passive"))
      (node (ref "C4") (pin "1") (pinfunction "1_1") (pintype "passive"))
      (node (ref "C42") (pin "1") (pinfunction "1_1") (pintype "passive"))
      (node (ref "C52") (pin "1") (pinfunction "1_1") (pintype "passive"))
      (node (ref "C6") (pin "1") (pinfunction "1_1") (pintype "passive"))
      (node (ref "D1") (pin "C") (pinfunction "C_C") (pintype "passive"))
      (node (ref "D2") (pin "C") (pinfunction "C_C") (pintype "passive"))
      (node (ref "D3") (pin "C") (pinfunction "C_C") (pintype "passive"))
      (node (ref "F1") (pin "3") (pinfunction "2_3") (pintype "passive"))
      (node (ref "F1") (pin "4") (pinfunction "2_4") (pintype "passive"))
      (node (ref "R11") (pin "2") (pinfunction "2_2") (pintype "passive"))
      (node (ref "R14") (pin "2") (pinfunction "2_2") (pintype "passive"))
      (node (ref "R15") (pin "2") (pinfunction "2_2") (pintype "passive"))
      (node (ref "R16") (pin "2") (pinfunction "2_2") (pintype "passive"))
      (node (ref "R45") (pin "1") (pinfunction "1_1") (pintype "passive"))
      (node (ref "R55") (pin "2") (pinfunction "2_2") (pintype "passive"))
      (node (ref "R56") (pin "2") (pinfunction "2_2") (pintype "passive"))
      (node (ref "R57") (pin "2") (pinfunction "2_2") (pintype "passive"))
      (node (ref "U10") (pin "4") (pinfunction "VIN_4") (pintype "power_in"))
      (node (ref "U13") (pin "11") (pinfunction "VMB_11") (pintype "power_in"))
      (node (ref "U13") (pin "4") (pinfunction "VMA_4") (pintype "power_in"))
      (node (ref "U14") (pin "11") (pinfunction "VMB_11") (pintype "power_in"))
      (node (ref "U14") (pin "4") (pinfunction "VMA_4") (pintype "power_in"))
      (node (ref "U15") (pin "11") (pinfunction "VMB_11") (pintype "power_in"))
      (node (ref "U15") (pin "4") (pinfunction "VMA_4") (pintype "power_in"))
      (node (ref "X1") (pin "1") (pinfunction "1_1") (pintype "passive"))
      (node (ref "X21") (pin "1") (pinfunction "1_1") (pintype "passive"))
      (node (ref "X3") (pin "1") (pinfunction "1_1") (pintype "passive"))
    )
    (net (code "32") (name "/VIN") (class "Default")
      (node (ref "F1") (pin "1") (pinfunction "1_1") (pintype "passive"))
      (node (ref "F1") (pin "2") (pinfunction "1_2") (pintype "passive"))
      (node (ref "LED8") (pin "A") (pinfunction "A_A") (pintype "passive"))
      (node (ref "X2") (pin "3") (pinfunction "1_3") (pintype "passive"))
      (node (ref "X2") (pin "4") (pinfunction "1_4") (pintype "passive"))
    )
    (net (code "33") (name "/VREF_EXT3") (class "Default")
      (node (ref "EXPAND") (pin "2") (pinfunction "2_2") (pintype "passive"))
      (node (ref "U13") (pin "12") (pinfunction "AVREF_12") (pintype "input"))
      (node (ref "U13") (pin "13") (pinfunction "BVREF_13") (pintype "input"))
    )
    (net (code "34") (name "/VREF_EXT4") (class "Default")
      (node (ref "EXPAND") (pin "4") (pinfunction "4_4") (pintype "passive"))
      (node (ref "U14") (pin "12") (pinfunction "AVREF_12") (pintype "input"))
      (node (ref "U14") (pin "13") (pinfunction "BVREF_13") (pintype "input"))
    )
    (net (code "35") (name "/VREF_EXT5") (class "Default")
      (node (ref "EXPAND") (pin "6") (pinfunction "6_6") (pintype "passive"))
      (node (ref "U15") (pin "12") (pinfunction "AVREF_12") (pintype "input"))
      (node (ref "U15") (pin "13") (pinfunction "BVREF_13") (pintype "input"))
    )
    (net (code "36") (name "AGND") (class "Default")
      (node (ref "C14") (pin "2") (pinfunction "2_2") (pintype "passive"))
      (node (ref "C15") (pin "2") (pinfunction "2_2") (pintype "passive"))
      (node (ref "C16") (pin "2") (pinfunction "2_2") (pintype "passive"))
      (node (ref "C26") (pin "2") (pinfunction "2_2") (pintype "passive"))
      (node (ref "C45") (pin "2") (pinfunction "2_2") (pintype "passive"))
      (node (ref "C46") (pin "2") (pinfunction "2_2") (pintype "passive"))
      (node (ref "P9") (pin "34") (pinfunction "34_34") (pintype "passive"))
      (node (ref "X7") (pin "2") (pinfunction "S_2") (pintype "passive"))
      (node (ref "X8") (pin "2") (pinfunction "S_2") (pintype "passive"))
      (node (ref "X9") (pin "2") (pinfunction "S_2") (pintype "passive"))
    )
    (net (code "37") (name "GND") (class "Default")
      (node (ref "C12") (pin "-") (pinfunction "-_-") (pintype "passive"))
      (node (ref "C13") (pin "2") (pinfunction "2_2") (pintype "passive"))
      (node (ref "C20") (pin "2") (pinfunction "2_2") (pintype "passive"))
      (node (ref "C21") (pin "2") (pinfunction "2_2") (pintype "passive"))
      (node (ref "C22") (pin "2") (pinfunction "2_2") (pintype "passive"))
      (node (ref "C23") (pin "2") (pinfunction "2_2") (pintype "passive"))
      (node (ref "C24") (pin "2") (pinfunction "2_2") (pintype "passive"))
      (node (ref "C25") (pin "2") (pinfunction "2_2") (pintype "passive"))
      (node (ref "C27") (pin "2") (pinfunction "2_2") (pintype "passive"))
      (node (ref "C30") (pin "2") (pinfunction "2_2") (pintype "passive"))
      (node (ref "C31") (pin "2") (pinfunction "2_2") (pintype "passive"))
      (node (ref "C32") (pin "2") (pinfunction "2_2") (pintype "passive"))
      (node (ref "C33") (pin "2") (pinfunction "2_2") (pintype "passive"))
      (node (ref "C34") (pin "2") (pinfunction "2_2") (pintype "passive"))
      (node (ref "C35") (pin "2") (pinfunction "2_2") (pintype "passive"))
      (node (ref "C38") (pin "2") (pinfunction "2_2") (pintype "passive"))
      (node (ref "C39") (pin "2") (pinfunction "2_2") (pintype "passive"))
      (node (ref "C40") (pin "2") (pinfunction "2_2") (pintype "passive"))
      (node (ref "C41") (pin "2") (pinfunction "2_2") (pintype "passive"))
      (node (ref "C42") (pin "2") (pinfunction "2_2") (pintype "passive"))
      (node (ref "C52") (pin "2") (pinfunction "2_2") (pintype "passive"))
      (node (ref "C53") (pin "2") (pinfunction "2_2") (pintype "passive"))
      (node (ref "C54") (pin "2") (pinfunction "2_2") (pintype "passive"))
      (node (ref "C57") (pin "2") (pinfunction "2_2") (pintype "passive"))
      (node (ref "C58") (pin "2") (pinfunction "2_2") (pintype "passive"))
      (node (ref "C59") (pin "2") (pinfunction "2_2") (pintype "passive"))
      (node (ref "D4") (pin "A") (pinfunction "A_A") (pintype "passive"))
      (node (ref "LED10") (pin "C") (pinfunction "C_C") (pintype "passive"))
      (node (ref "LED11") (pin "C") (pinfunction "C_C") (pintype "passive"))
      (node (ref "LED4") (pin "C") (pinfunction "C_C") (pintype "passive"))
      (node (ref "LED9") (pin "C") (pinfunction "C_C") (pintype "passive"))
      (node (ref "P8") (pin "1") (pinfunction "1_1") (pintype "passive"))
      (node (ref "P8") (pin "2") (pinfunction "2_2") (pintype "passive"))
      (node (ref "P9") (pin "1") (pinfunction "1_1") (pintype "passive"))
      (node (ref "P9") (pin "2") (pinfunction "2_2") (pintype "passive"))
      (node (ref "P9") (pin "43") (pinfunction "43_43") (pintype "passive"))
      (node (ref "P9") (pin "44") (pinfunction "44_44") (pintype "passive"))
      (node (ref "P9") (pin "45") (pinfunction "45_45") (pintype "passive"))
      (node (ref "P9") (pin "46") (pinfunction "46_46") (pintype "passive"))
      (node (ref "Q1") (pin "1") (pinfunction "S_1") (pintype "passive"))
      (node (ref "Q1") (pin "2") (pinfunction "S_2") (pintype "passive"))
      (node (ref "Q1") (pin "3") (pinfunction "S_3") (pintype "passive"))
      (node (ref "Q2") (pin "1") (pinfunction "S_1") (pintype "passive"))
      (node (ref "Q2") (pin "2") (pinfunction "S_2") (pintype "passive"))
      (node (ref "Q2") (pin "3") (pinfunction "S_3") (pintype "passive"))
      (node (ref "Q3") (pin "1") (pinfunction "S_1") (pintype "passive"))
      (node (ref "Q3") (pin "2") (pinfunction "S_2") (pintype "passive"))
      (node (ref "Q3") (pin "3") (pinfunction "S_3") (pintype "passive"))
      (node (ref "Q4") (pin "3") (pinfunction "S_3") (pintype "passive"))
      (node (ref "Q5") (pin "3") (pinfunction "S_3") (pintype "passive"))
      (node (ref "Q6") (pin "3") (pinfunction "S_3") (pintype "passive"))
      (node (ref "R1") (pin "1") (pinfunction "1_1") (pintype "passive"))
      (node (ref "R2") (pin "1") (pinfunction "1_1") (pintype "passive"))
      (node (ref "R3") (pin "1") (pinfunction "1_1") (pintype "passive"))
      (node (ref "R4") (pin "1") (pinfunction "1_1") (pintype "passive"))
      (node (ref "R43") (pin "2") (pinfunction "2_2") (pintype "passive"))
      (node (ref "R44") (pin "2") (pinfunction "2_2") (pintype "passive"))
      (node (ref "R46") (pin "1") (pinfunction "1_1") (pintype "passive"))
      (node (ref "R47") (pin "1") (pinfunction "1_1") (pintype "passive"))
      (node (ref "R48") (pin "1") (pinfunction "1_1") (pintype "passive"))
      (node (ref "R5") (pin "1") (pinfunction "1_1") (pintype "passive"))
      (node (ref "R6") (pin "1") (pinfunction "1_1") (pintype "passive"))
      (node (ref "S2") (pin "1") (pinfunction "1_1") (pintype "passive"))
      (node (ref "S2") (pin "2") (pinfunction "2_2") (pintype "passive"))
      (node (ref "U1") (pin "13") (pinfunction "~{OE}_13") (pintype "input"))
      (node (ref "U1") (pin "8") (pinfunction "GND_8") (pintype "passive"))
      (node (ref "U10") (pin "6") (pinfunction "GND_6") (pintype "power_in"))
      (node (ref "U10") (pin "EP") (pinfunction "EP_EP") (pintype "power_in"))
      (node (ref "U13") (pin "14") (pinfunction "GND_0_14") (pintype "power_in"))
      (node (ref "U13") (pin "28") (pinfunction "GND_1_28") (pintype "power_in"))
      (node (ref "U13") (pin "EXP") (pinfunction "GND_PAD_EXP") (pintype "power_in"))
      (node (ref "U14") (pin "14") (pinfunction "GND_0_14") (pintype "power_in"))
      (node (ref "U14") (pin "28") (pinfunction "GND_1_28") (pintype "power_in"))
      (node (ref "U14") (pin "EXP") (pinfunction "GND_PAD_EXP") (pintype "power_in"))
      (node (ref "U15") (pin "14") (pinfunction "GND_0_14") (pintype "power_in"))
      (node (ref "U15") (pin "28") (pinfunction "GND_1_28") (pintype "power_in"))
      (node (ref "U15") (pin "EXP") (pinfunction "GND_PAD_EXP") (pintype "power_in"))
      (node (ref "U18") (pin "4") (pinfunction "GND_4") (pintype "power_in"))
      (node (ref "U2") (pin "13") (pinfunction "~{OE}_13") (pintype "input"))
      (node (ref "U2") (pin "8") (pinfunction "GND_8") (pintype "passive"))
      (node (ref "U3") (pin "13") (pinfunction "~{OE}_13") (pintype "input"))
      (node (ref "U3") (pin "8") (pinfunction "GND_8") (pintype "passive"))
      (node (ref "U4") (pin "2") (pinfunction "GND_2") (pintype "passive"))
      (node (ref "U7") (pin "1") (pinfunction "GND_1") (pintype "power_in"))
      (node (ref "U7") (pin "4") (pinfunction "GND_4") (pintype "power_in"))
      (node (ref "U8") (pin "1") (pinfunction "GND_1") (pintype "power_in"))
      (node (ref "U8") (pin "4") (pinfunction "GND_4") (pintype "power_in"))
      (node (ref "U9") (pin "1") (pinfunction "GND_1") (pintype "power_in"))
      (node (ref "U9") (pin "4") (pinfunction "GND_4") (pintype "power_in"))
      (node (ref "X2") (pin "1") (pinfunction "1_1") (pintype "passive"))
      (node (ref "X2") (pin "2") (pinfunction "1_2") (pintype "passive"))
      (node (ref "X7") (pin "3") (pinfunction "S_3") (pintype "passive"))
      (node (ref "X8") (pin "3") (pinfunction "S_3") (pintype "passive"))
      (node (ref "X9") (pin "3") (pinfunction "S_3") (pintype "passive"))
    )
    (net (code "38") (name "Net-(C56-Pad2)") (class "Default")
      (node (ref "C56") (pin "2") (pinfunction "2_2") (pintype "passive"))
      (node (ref "R44") (pin "1") (pinfunction "1_1") (pintype "passive"))
    )
    (net (code "39") (name "Net-(LED1-PadA)") (class "Default")
      (node (ref "LED1") (pin "A") (pinfunction "A_A") (pintype "passive"))
      (node (ref "R14") (pin "1") (pinfunction "1_1") (pintype "passive"))
    )
    (net (code "40") (name "Net-(LED2-PadA)") (class "Default")
      (node (ref "LED2") (pin "A") (pinfunction "A_A") (pintype "passive"))
      (node (ref "R16") (pin "1") (pinfunction "1_1") (pintype "passive"))
    )
    (net (code "41") (name "Net-(LED3-PadA)") (class "Default")
      (node (ref "LED3") (pin "A") (pinfunction "A_A") (pintype "passive"))
      (node (ref "R15") (pin "1") (pinfunction "1_1") (pintype "passive"))
    )
    (net (code "42") (name "Net-(LED4-PadA)") (class "Default")
      (node (ref "LED4") (pin "A") (pinfunction "A_A") (pintype "passive"))
      (node (ref "R11") (pin "1") (pinfunction "1_1") (pintype "passive"))
    )
    (net (code "43") (name "Net-(LED5-PadA)") (class "Default")
      (node (ref "LED5") (pin "A") (pinfunction "A_A") (pintype "passive"))
      (node (ref "R19") (pin "1") (pinfunction "1_1") (pintype "passive"))
    )
    (net (code "44") (name "Net-(LED6-PadA)") (class "Default")
      (node (ref "LED6") (pin "A") (pinfunction "A_A") (pintype "passive"))
      (node (ref "R20") (pin "1") (pinfunction "1_1") (pintype "passive"))
    )
    (net (code "45") (name "Net-(LED7-PadA)") (class "Default")
      (node (ref "LED7") (pin "A") (pinfunction "A_A") (pintype "passive"))
      (node (ref "R21") (pin "1") (pinfunction "1_1") (pintype "passive"))
    )
    (net (code "46") (name "Net-(LED8-PadC)") (class "Default")
      (node (ref "LED8") (pin "C") (pinfunction "C_C") (pintype "passive"))
      (node (ref "R45") (pin "2") (pinfunction "2_2") (pintype "passive"))
    )
    (net (code "47") (name "Net-(LED9-PadA)") (class "Default")
      (node (ref "LED9") (pin "A") (pinfunction "A_A") (pintype "passive"))
      (node (ref "R7") (pin "1") (pinfunction "1_1") (pintype "passive"))
    )
    (net (code "48") (name "Net-(LED10-PadA)") (class "Default")
      (node (ref "LED10") (pin "A") (pinfunction "A_A") (pintype "passive"))
      (node (ref "R8") (pin "1") (pinfunction "1_1") (pintype "passive"))
    )
    (net (code "49") (name "Net-(LED11-PadA)") (class "Default")
      (node (ref "LED11") (pin "A") (pinfunction "A_A") (pintype "passive"))
      (node (ref "R9") (pin "1") (pinfunction "1_1") (pintype "passive"))
    )
    (net (code "50") (name "Net-(Q1-G)") (class "Default")
      (node (ref "Q1") (pin "4") (pinfunction "G_4") (pintype "passive"))
      (node (ref "R31") (pin "1") (pinfunction "1_1") (pintype "passive"))
    )
    (net (code "51") (name "Net-(Q2-G)") (class "Default")
      (node (ref "Q2") (pin "4") (pinfunction "G_4") (pintype "passive"))
      (node (ref "R37") (pin "1") (pinfunction "1_1") (pintype "passive"))
    )
    (net (code "52") (name "Net-(Q3-G)") (class "Default")
      (node (ref "Q3") (pin "4") (pinfunction "G_4") (pintype "passive"))
      (node (ref "R32") (pin "1") (pinfunction "1_1") (pintype "passive"))
    )
    (net (code "53") (name "Net-(U1-QB)") (class "Default")
      (node (ref "U1") (pin "1") (pinfunction "QB_1") (pintype "output"))
      (node (ref "U13") (pin "26") (pinfunction "MODE2_26") (pintype "input"))
    )
    (net (code "54") (name "Net-(U1-QC)") (class "Default")
      (node (ref "U1") (pin "2") (pinfunction "QC_2") (pintype "output"))
      (node (ref "U13") (pin "25") (pinfunction "MODE1_25") (pintype "input"))
    )
    (net (code "55") (name "Net-(U1-QD)") (class "Default")
      (node (ref "U1") (pin "3") (pinfunction "QD_3") (pintype "output"))
      (node (ref "U13") (pin "24") (pinfunction "MODE0_24") (pintype "input"))
    )
    (net (code "56") (name "Net-(U1-QE)") (class "Default")
      (node (ref "U1") (pin "4") (pinfunction "QE_4") (pintype "output"))
      (node (ref "U13") (pin "21") (pinfunction "ENBL_21") (pintype "input"))
    )
    (net (code "57") (name "Net-(U1-QF)") (class "Default")
      (node (ref "U1") (pin "5") (pinfunction "QF_5") (pintype "output"))
      (node (ref "U13") (pin "19") (pinfunction "DECAY_19") (pintype "input"))
    )
    (net (code "58") (name "Net-(U1-QG)") (class "Default")
      (node (ref "U1") (pin "6") (pinfunction "QG_6") (pintype "output"))
      (node (ref "U13") (pin "17") (pinfunction "SLEEP_17") (pintype "input"))
    )
    (net (code "59") (name "Net-(U1-QH)") (class "Default")
      (node (ref "U1") (pin "7") (pinfunction "QH_7") (pintype "output"))
      (node (ref "U13") (pin "16") (pinfunction "RESET_16") (pintype "input"))
    )
    (net (code "60") (name "Net-(U1-~{SRCLR})") (class "Default")
      (node (ref "R12") (pin "1") (pinfunction "1_1") (pintype "passive"))
      (node (ref "U1") (pin "10") (pinfunction "~{SRCLR}_10") (pintype "input"))
    )
    (net (code "61") (name "Net-(U2-~{SRCLR})") (class "Default")
      (node (ref "R35") (pin "1") (pinfunction "1_1") (pintype "passive"))
      (node (ref "U2") (pin "10") (pinfunction "~{SRCLR}_10") (pintype "input"))
    )
    (net (code "62") (name "Net-(U3-~{SRCLR})") (class "Default")
      (node (ref "R36") (pin "1") (pinfunction "1_1") (pintype "passive"))
      (node (ref "U3") (pin "10") (pinfunction "~{SRCLR}_10") (pintype "input"))
    )
    (net (code "63") (name "Net-(U7-O)") (class "Default")
      (node (ref "R37") (pin "2") (pinfunction "2_2") (pintype "passive"))
      (node (ref "U7") (pin "5") (pinfunction "O_5") (pintype "output"))
    )
    (net (code "64") (name "Net-(U8-O)") (class "Default")
      (node (ref "R31") (pin "2") (pinfunction "2_2") (pintype "passive"))
      (node (ref "U8") (pin "5") (pinfunction "O_5") (pintype "output"))
    )
    (net (code "65") (name "Net-(U9-O)") (class "Default")
      (node (ref "R32") (pin "2") (pinfunction "2_2") (pintype "passive"))
      (node (ref "U9") (pin "5") (pinfunction "O_5") (pintype "output"))
    )
    (net (code "66") (name "Net-(U10-BOOT)") (class "Default")
      (node (ref "C55") (pin "1") (pinfunction "1_1") (pintype "passive"))
      (node (ref "U10") (pin "2") (pinfunction "BOOT_2") (pintype "input"))
    )
    (net (code "67") (name "Net-(U10-COMP)") (class "Default")
      (node (ref "C56") (pin "1") (pinfunction "1_1") (pintype "passive"))
      (node (ref "U10") (pin "8") (pinfunction "COMP_8") (pintype "bidirectional"))
    )
    (net (code "68") (name "Net-(U10-FB)") (class "Default")
      (node (ref "R42") (pin "2") (pinfunction "2_2") (pintype "passive"))
      (node (ref "R43") (pin "1") (pinfunction "1_1") (pintype "passive"))
      (node (ref "U10") (pin "7") (pinfunction "FB_7") (pintype "input"))
    )
    (net (code "69") (name "Net-(U10-SS)") (class "Default")
      (node (ref "C54") (pin "1") (pinfunction "1_1") (pintype "passive"))
      (node (ref "U10") (pin "10") (pinfunction "SS_10") (pintype "bidirectional"))
    )
    (net (code "70") (name "Net-(U10-SW)") (class "Default")
      (node (ref "C55") (pin "2") (pinfunction "2_2") (pintype "passive"))
      (node (ref "D4") (pin "C") (pinfunction "C_C") (pintype "passive"))
      (node (ref "L2") (pin "P$2") (pinfunction "P$2_P$2") (pintype "passive"))
      (node (ref "U10") (pin "5") (pinfunction "SW_5") (pintype "power_in"))
    )
    (net (code "71") (name "Net-(U13-AOUT1)") (class "Default")
      (node (ref "U13") (pin "5") (pinfunction "AOUT1_5") (pintype "output"))
      (node (ref "X14") (pin "4") (pinfunction "S_4") (pintype "passive"))
    )
    (net (code "72") (name "Net-(U13-AOUT2)") (class "Default")
      (node (ref "U13") (pin "7") (pinfunction "AOUT2_7") (pintype "output"))
      (node (ref "X14") (pin "3") (pinfunction "S_3") (pintype "passive"))
    )
    (net (code "73") (name "Net-(U13-BOUT1)") (class "Default")
      (node (ref "U13") (pin "10") (pinfunction "BOUT1_10") (pintype "output"))
      (node (ref "X14") (pin "1") (pinfunction "S_1") (pintype "passive"))
    )
    (net (code "74") (name "Net-(U13-BOUT2)") (class "Default")
      (node (ref "U13") (pin "8") (pinfunction "BOUT2_8") (pintype "output"))
      (node (ref "X14") (pin "2") (pinfunction "S_2") (pintype "passive"))
    )
    (net (code "75") (name "Net-(U13-CP1)") (class "Default")
      (node (ref "C1") (pin "2") (pinfunction "2_2") (pintype "passive"))
      (node (ref "U13") (pin "1") (pinfunction "CP1_1") (pintype "bidirectional"))
    )
    (net (code "76") (name "Net-(U13-CP2)") (class "Default")
      (node (ref "C1") (pin "1") (pinfunction "1_1") (pintype "passive"))
      (node (ref "U13") (pin "2") (pinfunction "CP2_2") (pintype "bidirectional"))
    )
    (net (code "77") (name "Net-(U13-ISENA)") (class "Default")
      (node (ref "R2") (pin "2") (pinfunction "2_2") (pintype "passive"))
      (node (ref "U13") (pin "6") (pinfunction "ISENA_6") (pintype "output"))
    )
    (net (code "78") (name "Net-(U13-ISENB)") (class "Default")
      (node (ref "R1") (pin "2") (pinfunction "2_2") (pintype "passive"))
      (node (ref "U13") (pin "9") (pinfunction "ISENB_9") (pintype "output"))
    )
    (net (code "79") (name "Net-(U13-VCP)") (class "Default")
      (node (ref "C2") (pin "2") (pinfunction "2_2") (pintype "passive"))
      (node (ref "U13") (pin "3") (pinfunction "VCP_3") (pintype "bidirectional"))
    )
    (net (code "80") (name "Net-(U14-AOUT1)") (class "Default")
      (node (ref "U14") (pin "5") (pinfunction "AOUT1_5") (pintype "output"))
      (node (ref "X15") (pin "4") (pinfunction "S_4") (pintype "passive"))
    )
    (net (code "81") (name "Net-(U14-AOUT2)") (class "Default")
      (node (ref "U14") (pin "7") (pinfunction "AOUT2_7") (pintype "output"))
      (node (ref "X15") (pin "3") (pinfunction "S_3") (pintype "passive"))
    )
    (net (code "82") (name "Net-(U14-BOUT1)") (class "Default")
      (node (ref "U14") (pin "10") (pinfunction "BOUT1_10") (pintype "output"))
      (node (ref "X15") (pin "1") (pinfunction "S_1") (pintype "passive"))
    )
    (net (code "83") (name "Net-(U14-BOUT2)") (class "Default")
      (node (ref "U14") (pin "8") (pinfunction "BOUT2_8") (pintype "output"))
      (node (ref "X15") (pin "2") (pinfunction "S_2") (pintype "passive"))
    )
    (net (code "84") (name "Net-(U14-CP1)") (class "Default")
      (node (ref "C3") (pin "2") (pinfunction "2_2") (pintype "passive"))
      (node (ref "U14") (pin "1") (pinfunction "CP1_1") (pintype "bidirectional"))
    )
    (net (code "85") (name "Net-(U14-CP2)") (class "Default")
      (node (ref "C3") (pin "1") (pinfunction "1_1") (pintype "passive"))
      (node (ref "U14") (pin "2") (pinfunction "CP2_2") (pintype "bidirectional"))
    )
    (net (code "86") (name "Net-(U14-DECAY)") (class "Default")
      (node (ref "U14") (pin "19") (pinfunction "DECAY_19") (pintype "input"))
      (node (ref "U2") (pin "5") (pinfunction "QF_5") (pintype "output"))
    )
    (net (code "87") (name "Net-(U14-ENBL)") (class "Default")
      (node (ref "U14") (pin "21") (pinfunction "ENBL_21") (pintype "input"))
      (node (ref "U2") (pin "4") (pinfunction "QE_4") (pintype "output"))
    )
    (net (code "88") (name "Net-(U14-ISENA)") (class "Default")
      (node (ref "R4") (pin "2") (pinfunction "2_2") (pintype "passive"))
      (node (ref "U14") (pin "6") (pinfunction "ISENA_6") (pintype "output"))
    )
    (net (code "89") (name "Net-(U14-ISENB)") (class "Default")
      (node (ref "R3") (pin "2") (pinfunction "2_2") (pintype "passive"))
      (node (ref "U14") (pin "9") (pinfunction "ISENB_9") (pintype "output"))
    )
    (net (code "90") (name "Net-(U14-MODE0)") (class "Default")
      (node (ref "U14") (pin "24") (pinfunction "MODE0_24") (pintype "input"))
      (node (ref "U2") (pin "3") (pinfunction "QD_3") (pintype "output"))
    )
    (net (code "91") (name "Net-(U14-MODE1)") (class "Default")
      (node (ref "U14") (pin "25") (pinfunction "MODE1_25") (pintype "input"))
      (node (ref "U2") (pin "2") (pinfunction "QC_2") (pintype "output"))
    )
    (net (code "92") (name "Net-(U14-MODE2)") (class "Default")
      (node (ref "U14") (pin "26") (pinfunction "MODE2_26") (pintype "input"))
      (node (ref "U2") (pin "1") (pinfunction "QB_1") (pintype "output"))
    )
    (net (code "93") (name "Net-(U14-RESET)") (class "Default")
      (node (ref "U14") (pin "16") (pinfunction "RESET_16") (pintype "input"))
      (node (ref "U2") (pin "7") (pinfunction "QH_7") (pintype "output"))
    )
    (net (code "94") (name "Net-(U14-SLEEP)") (class "Default")
      (node (ref "U14") (pin "17") (pinfunction "SLEEP_17") (pintype "input"))
      (node (ref "U2") (pin "6") (pinfunction "QG_6") (pintype "output"))
    )
    (net (code "95") (name "Net-(U14-VCP)") (class "Default")
      (node (ref "C4") (pin "2") (pinfunction "2_2") (pintype "passive"))
      (node (ref "U14") (pin "3") (pinfunction "VCP_3") (pintype "bidirectional"))
    )
    (net (code "96") (name "Net-(U15-AOUT1)") (class "Default")
      (node (ref "U15") (pin "5") (pinfunction "AOUT1_5") (pintype "output"))
      (node (ref "X16") (pin "4") (pinfunction "S_4") (pintype "passive"))
    )
    (net (code "97") (name "Net-(U15-AOUT2)") (class "Default")
      (node (ref "U15") (pin "7") (pinfunction "AOUT2_7") (pintype "output"))
      (node (ref "X16") (pin "3") (pinfunction "S_3") (pintype "passive"))
    )
    (net (code "98") (name "Net-(U15-BOUT1)") (class "Default")
      (node (ref "U15") (pin "10") (pinfunction "BOUT1_10") (pintype "output"))
      (node (ref "X16") (pin "1") (pinfunction "S_1") (pintype "passive"))
    )
    (net (code "99") (name "Net-(U15-BOUT2)") (class "Default")
      (node (ref "U15") (pin "8") (pinfunction "BOUT2_8") (pintype "output"))
      (node (ref "X16") (pin "2") (pinfunction "S_2") (pintype "passive"))
    )
    (net (code "100") (name "Net-(U15-CP1)") (class "Default")
      (node (ref "C5") (pin "2") (pinfunction "2_2") (pintype "passive"))
      (node (ref "U15") (pin "1") (pinfunction "CP1_1") (pintype "bidirectional"))
    )
    (net (code "101") (name "Net-(U15-CP2)") (class "Default")
      (node (ref "C5") (pin "1") (pinfunction "1_1") (pintype "passive"))
      (node (ref "U15") (pin "2") (pinfunction "CP2_2") (pintype "bidirectional"))
    )
    (net (code "102") (name "Net-(U15-DECAY)") (class "Default")
      (node (ref "U15") (pin "19") (pinfunction "DECAY_19") (pintype "input"))
      (node (ref "U3") (pin "5") (pinfunction "QF_5") (pintype "output"))
    )
    (net (code "103") (name "Net-(U15-ENBL)") (class "Default")
      (node (ref "U15") (pin "21") (pinfunction "ENBL_21") (pintype "input"))
      (node (ref "U3") (pin "4") (pinfunction "QE_4") (pintype "output"))
    )
    (net (code "104") (name "Net-(U15-ISENA)") (class "Default")
      (node (ref "R6") (pin "2") (pinfunction "2_2") (pintype "passive"))
      (node (ref "U15") (pin "6") (pinfunction "ISENA_6") (pintype "output"))
    )
    (net (code "105") (name "Net-(U15-ISENB)") (class "Default")
      (node (ref "R5") (pin "2") (pinfunction "2_2") (pintype "passive"))
      (node (ref "U15") (pin "9") (pinfunction "ISENB_9") (pintype "output"))
    )
    (net (code "106") (name "Net-(U15-MODE0)") (class "Default")
      (node (ref "U15") (pin "24") (pinfunction "MODE0_24") (pintype "input"))
      (node (ref "U3") (pin "3") (pinfunction "QD_3") (pintype "output"))
    )
    (net (code "107") (name "Net-(U15-MODE1)") (class "Default")
      (node (ref "U15") (pin "25") (pinfunction "MODE1_25") (pintype "input"))
      (node (ref "U3") (pin "2") (pinfunction "QC_2") (pintype "output"))
    )
    (net (code "108") (name "Net-(U15-MODE2)") (class "Default")
      (node (ref "U15") (pin "26") (pinfunction "MODE2_26") (pintype "input"))
      (node (ref "U3") (pin "1") (pinfunction "QB_1") (pintype "output"))
    )
    (net (code "109") (name "Net-(U15-RESET)") (class "Default")
      (node (ref "U15") (pin "16") (pinfunction "RESET_16") (pintype "input"))
      (node (ref "U3") (pin "7") (pinfunction "QH_7") (pintype "output"))
    )
    (net (code "110") (name "Net-(U15-SLEEP)") (class "Default")
      (node (ref "U15") (pin "17") (pinfunction "SLEEP_17") (pintype "input"))
      (node (ref "U3") (pin "6") (pinfunction "QG_6") (pintype "output"))
    )
    (net (code "111") (name "Net-(U15-VCP)") (class "Default")
      (node (ref "C6") (pin "2") (pinfunction "2_2") (pintype "passive"))
      (node (ref "U15") (pin "3") (pinfunction "VCP_3") (pintype "bidirectional"))
    )
    (net (code "112") (name "Net-(U18-A0)") (class "Default")
      (node (ref "R24") (pin "1") (pinfunction "1_1") (pintype "passive"))
      (node (ref "S2") (pin "3") (pinfunction "3_3") (pintype "passive"))
      (node (ref "U18") (pin "1") (pinfunction "A0_1") (pintype "input"))
    )
    (net (code "113") (name "Net-(U18-A1)") (class "Default")
      (node (ref "R23") (pin "1") (pinfunction "1_1") (pintype "passive"))
      (node (ref "S2") (pin "4") (pinfunction "4_4") (pintype "passive"))
      (node (ref "U18") (pin "2") (pinfunction "A1_2") (pintype "input"))
    )
    (net (code "114") (name "Net-(U18-A2)") (class "Default")
      (node (ref "R22") (pin "1") (pinfunction "1_1") (pintype "passive"))
      (node (ref "U18") (pin "3") (pinfunction "A2_3") (pintype "input"))
    )
    (net (code "115") (name "Net-(X1B-1)") (class "Default")
      (node (ref "C58") (pin "1") (pinfunction "1_1") (pintype "passive"))
      (node (ref "D2") (pin "A") (pinfunction "A_A") (pintype "passive"))
      (node (ref "LED2") (pin "C") (pinfunction "C_C") (pintype "passive"))
      (node (ref "Q1") (pin "5") (pinfunction "D_5") (pintype "passive"))
      (node (ref "Q1") (pin "6") (pinfunction "D_6") (pintype "passive"))
      (node (ref "Q1") (pin "7") (pinfunction "D_7") (pintype "passive"))
      (node (ref "Q1") (pin "8") (pinfunction "D_8") (pintype "passive"))
      (node (ref "Q1") (pin "TH") (pinfunction "D_TH") (pintype "passive"))
      (node (ref "R56") (pin "1") (pinfunction "1_1") (pintype "passive"))
      (node (ref "X1") (pin "2") (pinfunction "1_2") (pintype "passive"))
    )
    (net (code "116") (name "Net-(X3B-1)") (class "Default")
      (node (ref "C59") (pin "1") (pinfunction "1_1") (pintype "passive"))
      (node (ref "D1") (pin "A") (pinfunction "A_A") (pintype "passive"))
      (node (ref "LED3") (pin "C") (pinfunction "C_C") (pintype "passive"))
      (node (ref "Q3") (pin "5") (pinfunction "D_5") (pintype "passive"))
      (node (ref "Q3") (pin "6") (pinfunction "D_6") (pintype "passive"))
      (node (ref "Q3") (pin "7") (pinfunction "D_7") (pintype "passive"))
      (node (ref "Q3") (pin "8") (pinfunction "D_8") (pintype "passive"))
      (node (ref "Q3") (pin "TH") (pinfunction "D_TH") (pintype "passive"))
      (node (ref "R55") (pin "1") (pinfunction "1_1") (pintype "passive"))
      (node (ref "X3") (pin "2") (pinfunction "1_2") (pintype "passive"))
    )
    (net (code "117") (name "Net-(X4B-S)") (class "Default")
      (node (ref "LED5") (pin "C") (pinfunction "C_C") (pintype "passive"))
      (node (ref "Q4") (pin "2") (pinfunction "D_2") (pintype "passive"))
      (node (ref "Q4") (pin "4") (pinfunction "D_4") (pintype "passive"))
      (node (ref "X4") (pin "2") (pinfunction "S_2") (pintype "passive"))
    )
    (net (code "118") (name "Net-(X5B-S)") (class "Default")
      (node (ref "LED6") (pin "C") (pinfunction "C_C") (pintype "passive"))
      (node (ref "Q5") (pin "2") (pinfunction "D_2") (pintype "passive"))
      (node (ref "Q5") (pin "4") (pinfunction "D_4") (pintype "passive"))
      (node (ref "X5") (pin "2") (pinfunction "S_2") (pintype "passive"))
    )
    (net (code "119") (name "Net-(X6B-S)") (class "Default")
      (node (ref "LED7") (pin "C") (pinfunction "C_C") (pintype "passive"))
      (node (ref "Q6") (pin "2") (pinfunction "D_2") (pintype "passive"))
      (node (ref "Q6") (pin "4") (pinfunction "D_4") (pintype "passive"))
      (node (ref "X6") (pin "2") (pinfunction "S_2") (pintype "passive"))
    )
    (net (code "120") (name "Net-(X7A-S)") (class "Default")
      (node (ref "C16") (pin "1") (pinfunction "1_1") (pintype "passive"))
      (node (ref "R18") (pin "1") (pinfunction "1_1") (pintype "passive"))
      (node (ref "R40") (pin "1") (pinfunction "1_1") (pintype "passive"))
      (node (ref "X7") (pin "1") (pinfunction "S_1") (pintype "passive"))
    )
    (net (code "121") (name "Net-(X8A-S)") (class "Default")
      (node (ref "C15") (pin "1") (pinfunction "1_1") (pintype "passive"))
      (node (ref "R17") (pin "1") (pinfunction "1_1") (pintype "passive"))
      (node (ref "R39") (pin "1") (pinfunction "1_1") (pintype "passive"))
      (node (ref "X8") (pin "1") (pinfunction "S_1") (pintype "passive"))
    )
    (net (code "122") (name "Net-(X9A-S)") (class "Default")
      (node (ref "C14") (pin "1") (pinfunction "1_1") (pintype "passive"))
      (node (ref "R13") (pin "1") (pinfunction "1_1") (pintype "passive"))
      (node (ref "R38") (pin "1") (pinfunction "1_1") (pintype "passive"))
      (node (ref "X9") (pin "1") (pinfunction "S_1") (pintype "passive"))
    )
    (net (code "123") (name "Net-(X21B-1)") (class "Default")
      (node (ref "C57") (pin "1") (pinfunction "1_1") (pintype "passive"))
      (node (ref "D3") (pin "A") (pinfunction "A_A") (pintype "passive"))
      (node (ref "LED1") (pin "C") (pinfunction "C_C") (pintype "passive"))
      (node (ref "Q2") (pin "5") (pinfunction "D_5") (pintype "passive"))
      (node (ref "Q2") (pin "6") (pinfunction "D_6") (pintype "passive"))
      (node (ref "Q2") (pin "7") (pinfunction "D_7") (pintype "passive"))
      (node (ref "Q2") (pin "8") (pinfunction "D_8") (pintype "passive"))
      (node (ref "Q2") (pin "TH") (pinfunction "D_TH") (pintype "passive"))
      (node (ref "R57") (pin "1") (pinfunction "1_1") (pintype "passive"))
      (node (ref "X21") (pin "2") (pinfunction "1_2") (pintype "passive"))
    )
    (net (code "124") (name "unconnected-(P8-Pad3)") (class "Default")
      (node (ref "P8") (pin "3") (pinfunction "3_3") (pintype "passive"))
    )
    (net (code "125") (name "unconnected-(P8-Pad4)") (class "Default")
      (node (ref "P8") (pin "4") (pinfunction "4_4") (pintype "passive"))
    )
    (net (code "126") (name "unconnected-(P8-Pad5)") (class "Default")
      (node (ref "P8") (pin "5") (pinfunction "5_5") (pintype "passive"))
    )
    (net (code "127") (name "unconnected-(P8-Pad6)") (class "Default")
      (node (ref "P8") (pin "6") (pinfunction "6_6") (pintype "passive"))
    )
    (net (code "128") (name "unconnected-(P8-Pad8)") (class "Default")
      (node (ref "P8") (pin "8") (pinfunction "8_8") (pintype "passive"))
    )
    (net (code "129") (name "unconnected-(P8-Pad9)") (class "Default")
      (node (ref "P8") (pin "9") (pinfunction "9_9") (pintype "passive"))
    )
    (net (code "130") (name "unconnected-(P8-Pad10)") (class "Default")
      (node (ref "P8") (pin "10") (pinfunction "10_10") (pintype "passive"))
    )
    (net (code "131") (name "unconnected-(P8-Pad11)") (class "Default")
      (node (ref "P8") (pin "11") (pinfunction "11_11") (pintype "passive"))
    )
    (net (code "132") (name "unconnected-(P8-Pad12)") (class "Default")
      (node (ref "P8") (pin "12") (pinfunction "12_12") (pintype "passive"))
    )
    (net (code "133") (name "unconnected-(P8-Pad13)") (class "Default")
      (node (ref "P8") (pin "13") (pinfunction "13_13") (pintype "passive"))
    )
    (net (code "134") (name "unconnected-(P8-Pad14)") (class "Default")
      (node (ref "P8") (pin "14") (pinfunction "14_14") (pintype "passive"))
    )
    (net (code "135") (name "unconnected-(P8-Pad15)") (class "Default")
      (node (ref "P8") (pin "15") (pinfunction "15_15") (pintype "passive"))
    )
    (net (code "136") (name "unconnected-(P8-Pad16)") (class "Default")
      (node (ref "P8") (pin "16") (pinfunction "16_16") (pintype "passive"))
    )
    (net (code "137") (name "unconnected-(P8-Pad17)") (class "Default")
      (node (ref "P8") (pin "17") (pinfunction "17_17") (pintype "passive"))
    )
    (net (code "138") (name "unconnected-(P8-Pad18)") (class "Default")
      (node (ref "P8") (pin "18") (pinfunction "18_18") (pintype "passive"))
    )
    (net (code "139") (name "unconnected-(P8-Pad19)") (class "Default")
      (node (ref "P8") (pin "19") (pinfunction "19_19") (pintype "passive"))
    )
    (net (code "140") (name "unconnected-(P8-Pad20)") (class "Default")
      (node (ref "P8") (pin "20") (pinfunction "20_20") (pintype "passive"))
    )
    (net (code "141") (name "unconnected-(P8-Pad21)") (class "Default")
      (node (ref "P8") (pin "21") (pinfunction "21_21") (pintype "passive"))
    )
    (net (code "142") (name "unconnected-(P8-Pad22)") (class "Default")
      (node (ref "P8") (pin "22") (pinfunction "22_22") (pintype "passive"))
    )
    (net (code "143") (name "unconnected-(P8-Pad23)") (class "Default")
      (node (ref "P8") (pin "23") (pinfunction "23_23") (pintype "passive"))
    )
    (net (code "144") (name "unconnected-(P8-Pad24)") (class "Default")
      (node (ref "P8") (pin "24") (pinfunction "24_24") (pintype "passive"))
    )
    (net (code "145") (name "unconnected-(P8-Pad25)") (class "Default")
      (node (ref "P8") (pin "25") (pinfunction "25_25") (pintype "passive"))
    )
    (net (code "146") (name "unconnected-(P8-Pad26)") (class "Default")
      (node (ref "P8") (pin "26") (pinfunction "26_26") (pintype "passive"))
    )
    (net (code "147") (name "unconnected-(P8-Pad27)") (class "Default")
      (node (ref "P8") (pin "27") (pinfunction "27_27") (pintype "passive"))
    )
    (net (code "148") (name "unconnected-(P8-Pad28)") (class "Default")
      (node (ref "P8") (pin "28") (pinfunction "28_28") (pintype "passive"))
    )
    (net (code "149") (name "unconnected-(P8-Pad29)") (class "Default")
      (node (ref "P8") (pin "29") (pinfunction "29_29") (pintype "passive"))
    )
    (net (code "150") (name "unconnected-(P8-Pad30)") (class "Default")
      (node (ref "P8") (pin "30") (pinfunction "30_30") (pintype "passive"))
    )
    (net (code "151") (name "unconnected-(P8-Pad31)") (class "Default")
      (node (ref "P8") (pin "31") (pinfunction "31_31") (pintype "passive"))
    )
    (net (code "152") (name "unconnected-(P8-Pad32)") (class "Default")
      (node (ref "P8") (pin "32") (pinfunction "32_32") (pintype "passive"))
    )
    (net (code "153") (name "unconnected-(P8-Pad33)") (class "Default")
      (node (ref "P8") (pin "33") (pinfunction "33_33") (pintype "passive"))
    )
    (net (code "154") (name "unconnected-(P8-Pad34)") (class "Default")
      (node (ref "P8") (pin "34") (pinfunction "34_34") (pintype "passive"))
    )
    (net (code "155") (name "unconnected-(P8-Pad35)") (class "Default")
      (node (ref "P8") (pin "35") (pinfunction "35_35") (pintype "passive"))
    )
    (net (code "156") (name "unconnected-(P8-Pad36)") (class "Default")
      (node (ref "P8") (pin "36") (pinfunction "36_36") (pintype "passive"))
    )
    (net (code "157") (name "unconnected-(P8-Pad37)") (class "Default")
      (node (ref "P8") (pin "37") (pinfunction "37_37") (pintype "passive"))
    )
    (net (code "158") (name "unconnected-(P8-Pad38)") (class "Default")
      (node (ref "P8") (pin "38") (pinfunction "38_38") (pintype "passive"))
    )
    (net (code "159") (name "unconnected-(P8-Pad39)") (class "Default")
      (node (ref "P8") (pin "39") (pinfunction "39_39") (pintype "passive"))
    )
    (net (code "160") (name "unconnected-(P8-Pad40)") (class "Default")
      (node (ref "P8") (pin "40") (pinfunction "40_40") (pintype "passive"))
    )
    (net (code "161") (name "unconnected-(P8-Pad41)") (class "Default")
      (node (ref "P8") (pin "41") (pinfunction "41_41") (pintype "passive"))
    )
    (net (code "162") (name "unconnected-(P8-Pad42)") (class "Default")
      (node (ref "P8") (pin "42") (pinfunction "42_42") (pintype "passive"))
    )
    (net (code "163") (name "unconnected-(P8-Pad43)") (class "Default")
      (node (ref "P8") (pin "43") (pinfunction "43_43") (pintype "passive"))
    )
    (net (code "164") (name "unconnected-(P8-Pad44)") (class "Default")
      (node (ref "P8") (pin "44") (pinfunction "44_44") (pintype "passive"))
    )
    (net (code "165") (name "unconnected-(P8-Pad45)") (class "Default")
      (node (ref "P8") (pin "45") (pinfunction "45_45") (pintype "passive"))
    )
    (net (code "166") (name "unconnected-(P8-Pad46)") (class "Default")
      (node (ref "P8") (pin "46") (pinfunction "46_46") (pintype "passive"))
    )
    (net (code "167") (name "unconnected-(P9-Pad7)") (class "Default")
      (node (ref "P9") (pin "7") (pinfunction "7_7") (pintype "passive"))
    )
    (net (code "168") (name "unconnected-(P9-Pad8)") (class "Default")
      (node (ref "P9") (pin "8") (pinfunction "8_8") (pintype "passive"))
    )
    (net (code "169") (name "unconnected-(P9-Pad9)") (class "Default")
      (node (ref "P9") (pin "9") (pinfunction "9_9") (pintype "passive"))
    )
    (net (code "170") (name "unconnected-(P9-Pad10)") (class "Default")
      (node (ref "P9") (pin "10") (pinfunction "10_10") (pintype "passive"))
    )
    (net (code "171") (name "unconnected-(P9-Pad11)") (class "Default")
      (node (ref "P9") (pin "11") (pinfunction "11_11") (pintype "passive"))
    )
    (net (code "172") (name "unconnected-(P9-Pad12)") (class "Default")
      (node (ref "P9") (pin "12") (pinfunction "12_12") (pintype "passive"))
    )
    (net (code "173") (name "unconnected-(P9-Pad13)") (class "Default")
      (node (ref "P9") (pin "13") (pinfunction "13_13") (pintype "passive"))
    )
    (net (code "174") (name "unconnected-(P9-Pad16)") (class "Default")
      (node (ref "P9") (pin "16") (pinfunction "16_16") (pintype "passive"))
    )
    (net (code "175") (name "unconnected-(P9-Pad18)") (class "Default")
      (node (ref "P9") (pin "18") (pinfunction "18_18") (pintype "passive"))
    )
    (net (code "176") (name "unconnected-(P9-Pad22)") (class "Default")
      (node (ref "P9") (pin "22") (pinfunction "22_22") (pintype "passive"))
    )
    (net (code "177") (name "unconnected-(P9-Pad23)") (class "Default")
      (node (ref "P9") (pin "23") (pinfunction "23_23") (pintype "passive"))
    )
    (net (code "178") (name "unconnected-(P9-Pad24)") (class "Default")
      (node (ref "P9") (pin "24") (pinfunction "24_24") (pintype "passive"))
    )
    (net (code "179") (name "unconnected-(P9-Pad25)") (class "Default")
      (node (ref "P9") (pin "25") (pinfunction "25_25") (pintype "passive"))
    )
    (net (code "180") (name "unconnected-(P9-Pad26)") (class "Default")
      (node (ref "P9") (pin "26") (pinfunction "26_26") (pintype "passive"))
    )
    (net (code "181") (name "unconnected-(P9-Pad28)") (class "Default")
      (node (ref "P9") (pin "28") (pinfunction "28_28") (pintype "passive"))
    )
    (net (code "182") (name "unconnected-(P9-Pad30)") (class "Default")
      (node (ref "P9") (pin "30") (pinfunction "30_30") (pintype "passive"))
    )
    (net (code "183") (name "unconnected-(P9-Pad33)") (class "Default")
      (node (ref "P9") (pin "33") (pinfunction "33_33") (pintype "passive"))
    )
    (net (code "184") (name "unconnected-(P9-Pad35)") (class "Default")
      (node (ref "P9") (pin "35") (pinfunction "35_35") (pintype "passive"))
    )
    (net (code "185") (name "unconnected-(P9-Pad36)") (class "Default")
      (node (ref "P9") (pin "36") (pinfunction "36_36") (pintype "passive"))
    )
    (net (code "186") (name "unconnected-(P9-Pad40)") (class "Default")
      (node (ref "P9") (pin "40") (pinfunction "40_40") (pintype "passive"))
    )
    (net (code "187") (name "unconnected-(P9-Pad41)") (class "Default")
      (node (ref "P9") (pin "41") (pinfunction "41_41") (pintype "passive"))
    )
    (net (code "188") (name "unconnected-(U1-QA-Pad15)") (class "Default")
      (node (ref "U1") (pin "15") (pinfunction "QA_15") (pintype "output"))
    )
    (net (code "189") (name "unconnected-(U2-QA-Pad15)") (class "Default")
      (node (ref "U2") (pin "15") (pinfunction "QA_15") (pintype "output"))
    )
    (net (code "190") (name "unconnected-(U3-QA-Pad15)") (class "Default")
      (node (ref "U3") (pin "15") (pinfunction "QA_15") (pintype "output"))
    )
    (net (code "191") (name "unconnected-(U3-QH_2-Pad9)") (class "Default")
      (node (ref "U3") (pin "9") (pinfunction "QH_2_9") (pintype "output"))
    )
    (net (code "192") (name "unconnected-(U10-EN-Pad9)") (class "Default")
      (node (ref "U10") (pin "9") (pinfunction "EN_9") (pintype "input"))
    )
    (net (code "193") (name "unconnected-(U13-HOME-Pad27)") (class "Default")
      (node (ref "U13") (pin "27") (pinfunction "HOME_27") (pintype "output"))
    )
    (net (code "194") (name "unconnected-(U13-V3P3OUT-Pad15)") (class "Default")
      (node (ref "U13") (pin "15") (pinfunction "V3P3OUT_15") (pintype "output"))
    )
    (net (code "195") (name "unconnected-(U14-HOME-Pad27)") (class "Default")
      (node (ref "U14") (pin "27") (pinfunction "HOME_27") (pintype "output"))
    )
    (net (code "196") (name "unconnected-(U14-V3P3OUT-Pad15)") (class "Default")
      (node (ref "U14") (pin "15") (pinfunction "V3P3OUT_15") (pintype "output"))
    )
    (net (code "197") (name "unconnected-(U15-HOME-Pad27)") (class "Default")
      (node (ref "U15") (pin "27") (pinfunction "HOME_27") (pintype "output"))
    )
    (net (code "198") (name "unconnected-(U15-V3P3OUT-Pad15)") (class "Default")
      (node (ref "U15") (pin "15") (pinfunction "V3P3OUT_15") (pintype "output"))
    )
    (net (code "199") (name "unconnected-(U18-~{WC}-Pad7)") (class "Default")
      (node (ref "U18") (pin "7") (pinfunction "~{WC}_7") (pintype "no_connect"))
    )
  )
)
